# openmv-mp.net
KiCad netlist of a schematic drawn in EAGLE
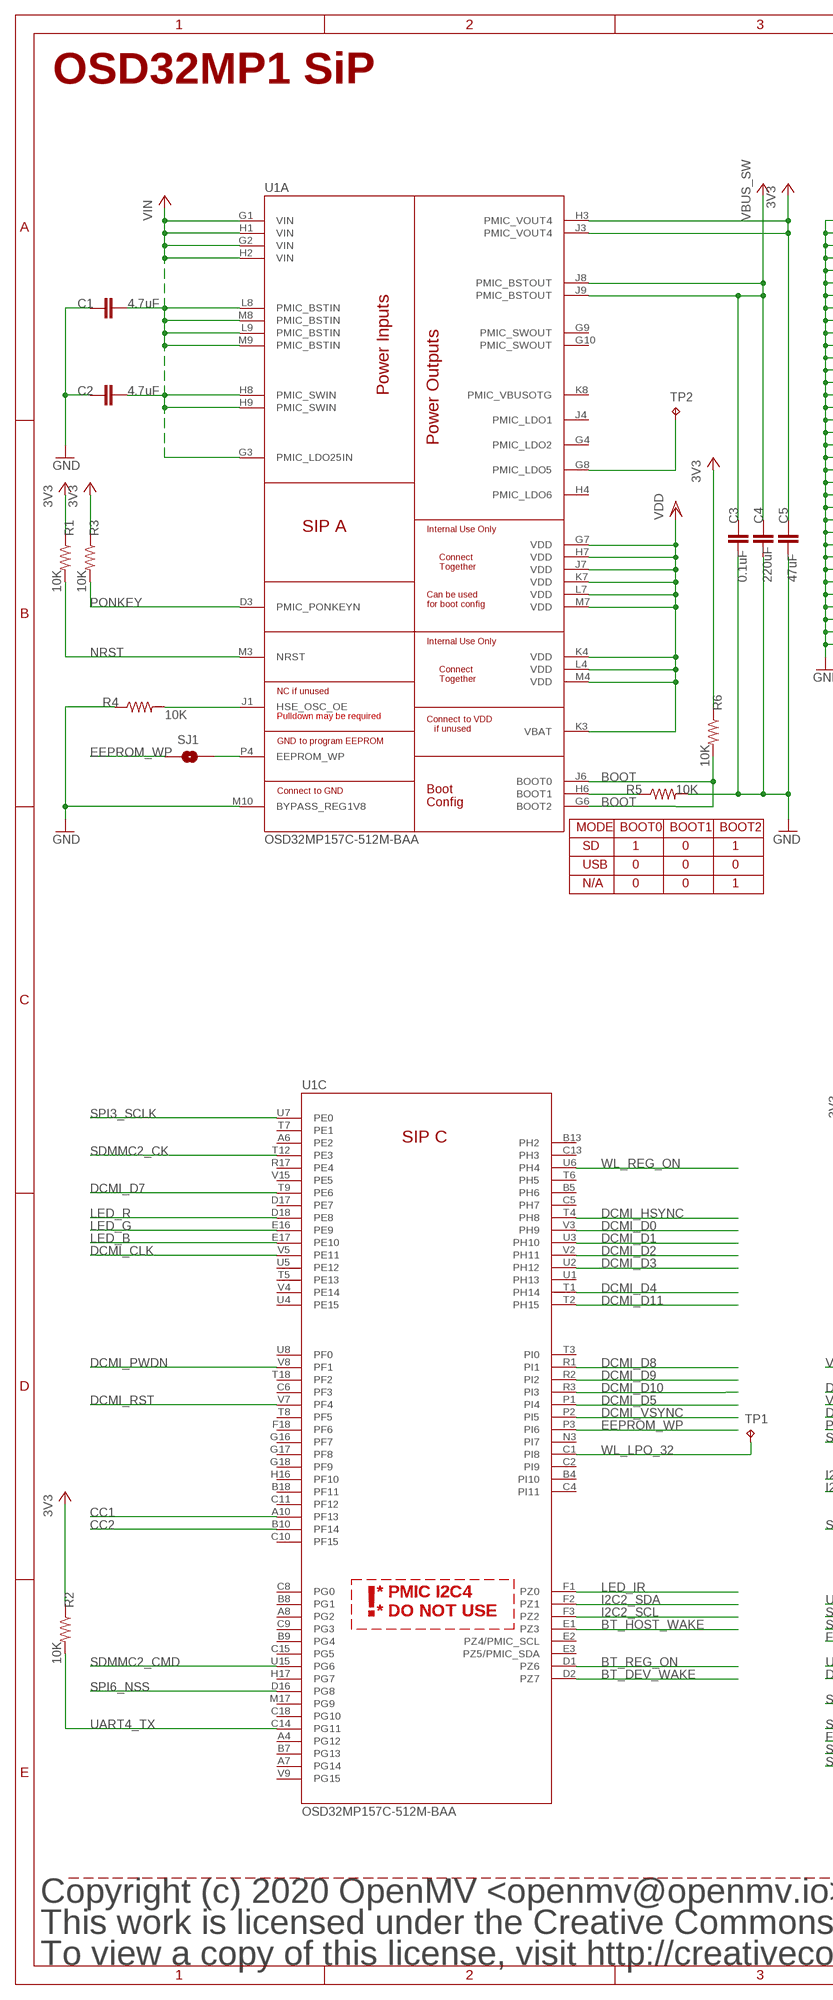
[diagram p0: schematic, sheet 1, part 1 of 2]
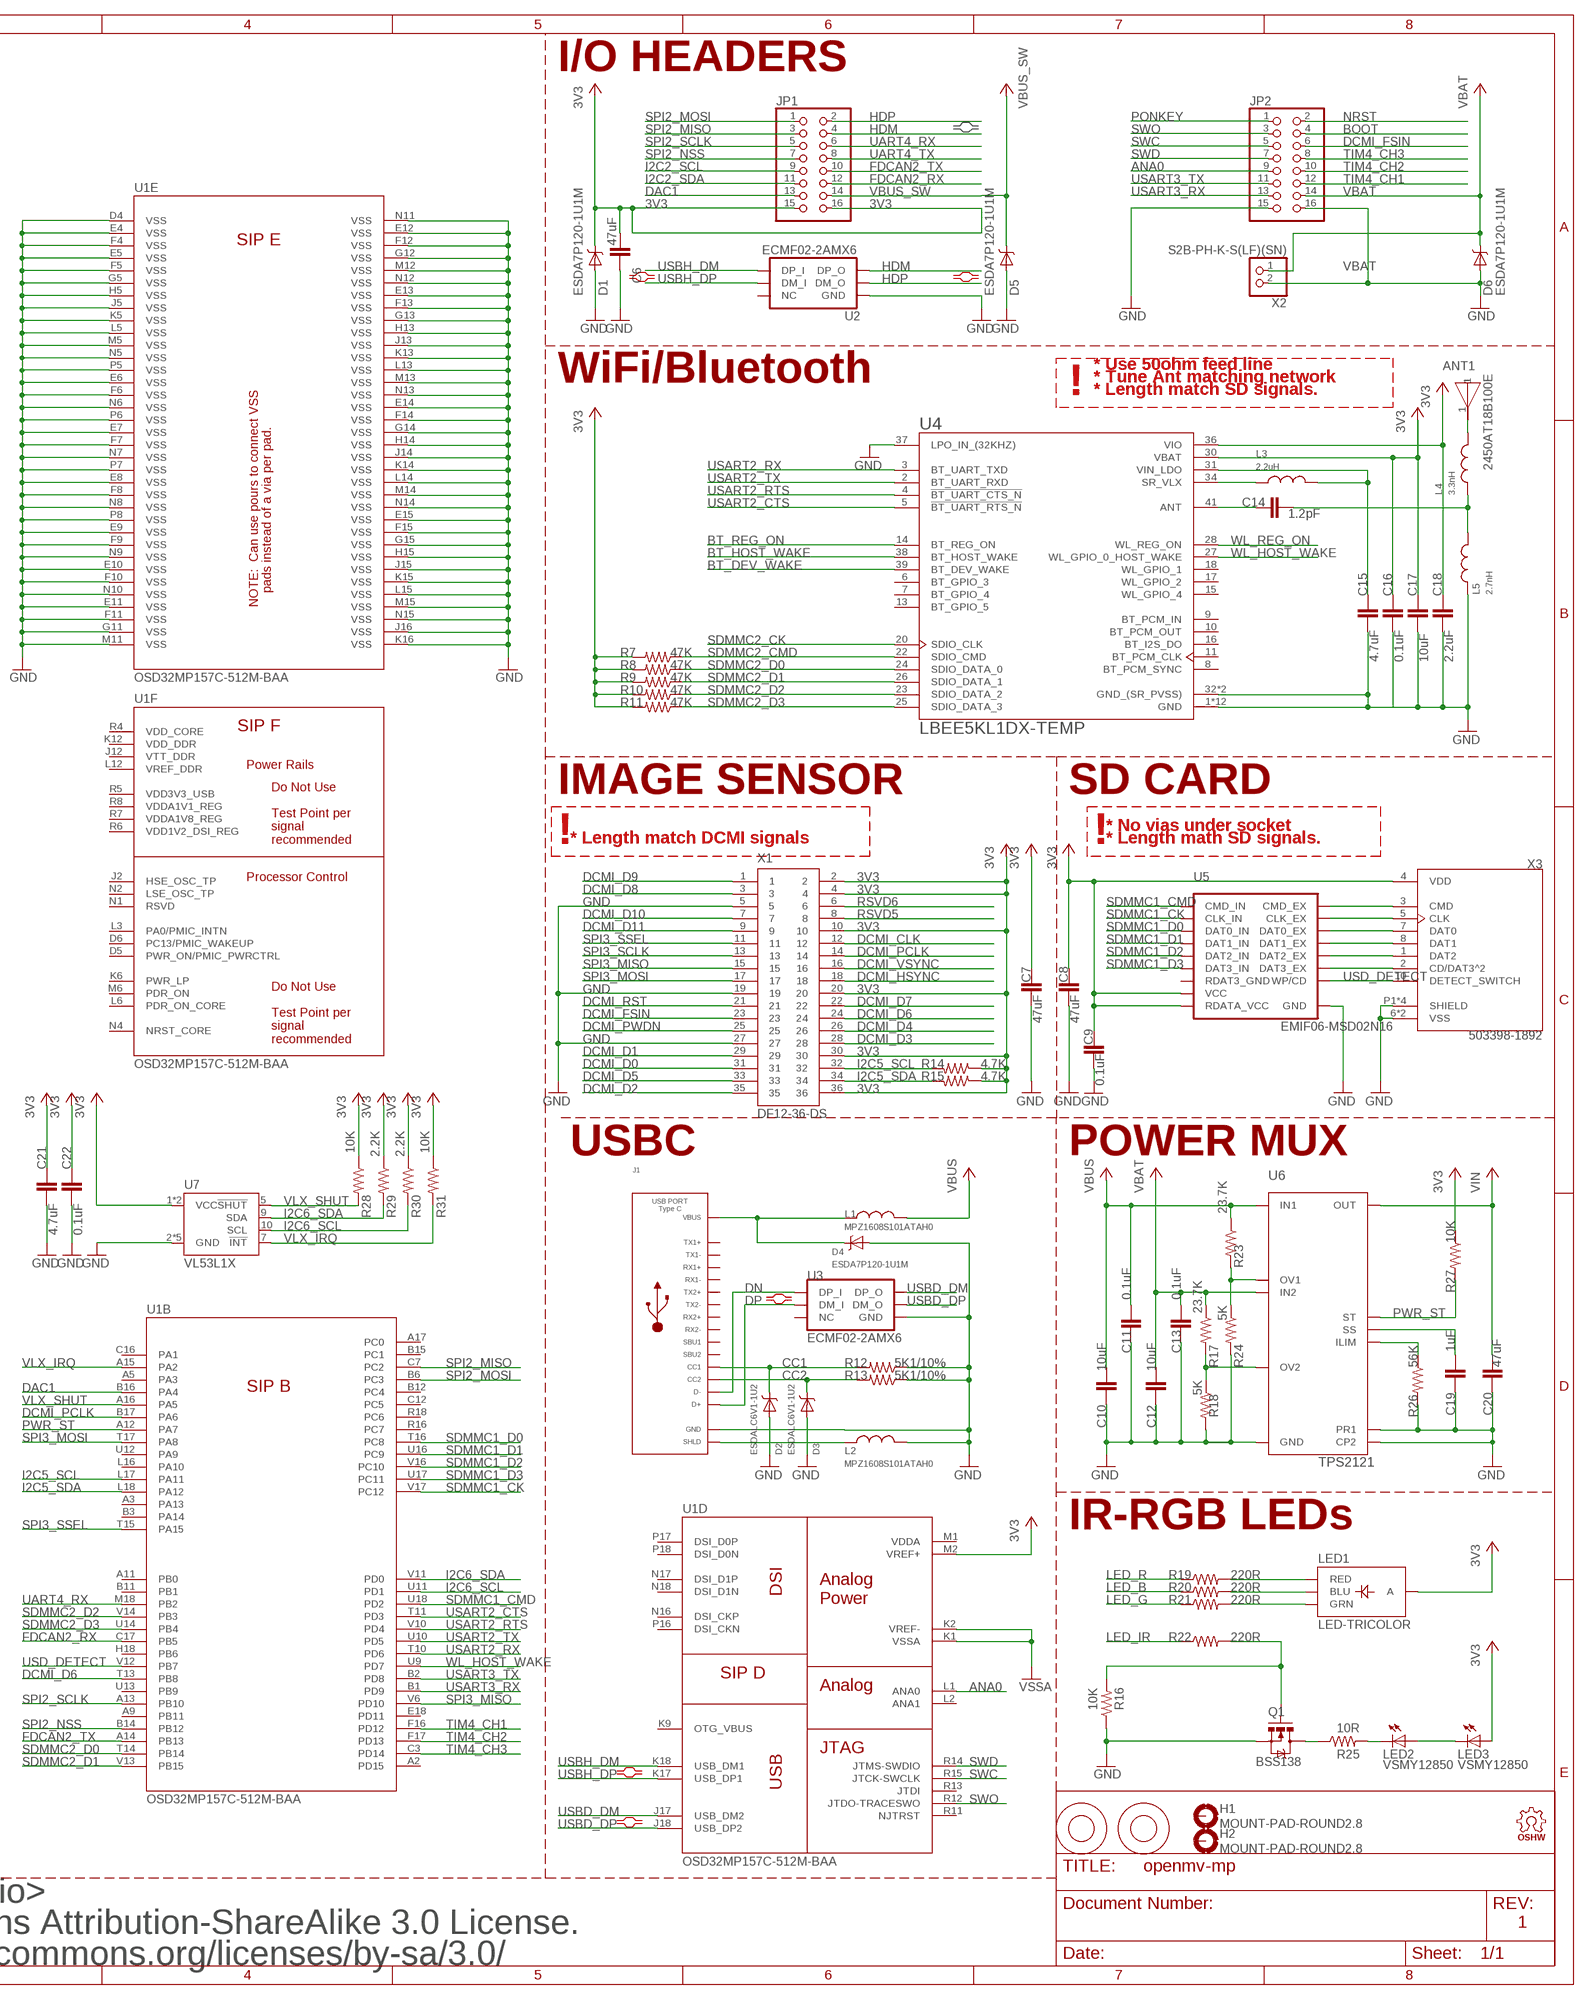
[diagram p1: schematic, sheet 1, part 2 of 2]

(export (version "E")
  (design (tool "Eeschema 10.0.6"))
  (components
    (comp (ref "ANT1")
      (value "2450AT18B100E")
      (footprint "eagle-import:ANT_2450AT18B100E")
      (fields (field (name "MF") "Johanson Technology"))
      (libsource (lib "eagle-import") (part "2450AT18B100E"))
    )
    (comp (ref "C1")
      (value "4.7uF")
      (footprint "eagle-import:0402-CAP")
      (libsource (lib "eagle-import") (part "CAP0402-CAP"))
    )
    (comp (ref "C2")
      (value "4.7uF")
      (footprint "eagle-import:0402-CAP")
      (libsource (lib "eagle-import") (part "CAP0402-CAP"))
    )
    (comp (ref "C3")
      (value "0.1uF")
      (footprint "eagle-import:0402-CAP")
      (libsource (lib "eagle-import") (part "CAP0402-CAP"))
    )
    (comp (ref "C4")
      (value "220uF")
      (footprint "eagle-import:1206")
      (libsource (lib "eagle-import") (part "CAP1206"))
    )
    (comp (ref "C5")
      (value "47uF")
      (footprint "eagle-import:0805")
      (libsource (lib "eagle-import") (part "CAP0805"))
    )
    (comp (ref "C6")
      (value "47uF")
      (footprint "eagle-import:0805")
      (libsource (lib "eagle-import") (part "CAP0805"))
    )
    (comp (ref "C7")
      (value "47uF")
      (footprint "eagle-import:0805")
      (libsource (lib "eagle-import") (part "CAP0805"))
    )
    (comp (ref "C8")
      (value "47uF")
      (footprint "eagle-import:0805")
      (libsource (lib "eagle-import") (part "CAP0805"))
    )
    (comp (ref "C9")
      (value "0.1uF")
      (footprint "eagle-import:0402-CAP")
      (libsource (lib "eagle-import") (part "CAP0402-CAP"))
    )
    (comp (ref "C10")
      (value "10uF")
      (footprint "eagle-import:0402-CAP")
      (libsource (lib "eagle-import") (part "CAP0402-CAP"))
    )
    (comp (ref "C11")
      (value "0.1uF")
      (footprint "eagle-import:0402-CAP")
      (libsource (lib "eagle-import") (part "CAP0402-CAP"))
    )
    (comp (ref "C12")
      (value "10uF")
      (footprint "eagle-import:0402-CAP")
      (libsource (lib "eagle-import") (part "CAP0402-CAP"))
    )
    (comp (ref "C13")
      (value "0.1uF")
      (footprint "eagle-import:0402-CAP")
      (libsource (lib "eagle-import") (part "CAP0402-CAP"))
    )
    (comp (ref "C14")
      (value "1.2pF")
      (footprint "eagle-import:0402-CAP")
      (libsource (lib "eagle-import") (part "CAP0402-CAP"))
    )
    (comp (ref "C15")
      (value "4.7uF")
      (footprint "eagle-import:0402-CAP")
      (libsource (lib "eagle-import") (part "CAP0402-CAP"))
    )
    (comp (ref "C16")
      (value "0.1uF")
      (footprint "eagle-import:0402-CAP")
      (libsource (lib "eagle-import") (part "CAP0402-CAP"))
    )
    (comp (ref "C17")
      (value "10uF")
      (footprint "eagle-import:0402-CAP")
      (libsource (lib "eagle-import") (part "CAP0402-CAP"))
    )
    (comp (ref "C18")
      (value "2.2uF")
      (footprint "eagle-import:0402-CAP")
      (libsource (lib "eagle-import") (part "CAP0402-CAP"))
    )
    (comp (ref "C19")
      (value "1uF")
      (footprint "eagle-import:0402-CAP")
      (libsource (lib "eagle-import") (part "CAP0402-CAP"))
    )
    (comp (ref "C20")
      (value "47uF")
      (footprint "eagle-import:0805")
      (libsource (lib "eagle-import") (part "CAP0805"))
    )
    (comp (ref "C21")
      (value "4.7uF")
      (footprint "eagle-import:0402-CAP")
      (libsource (lib "eagle-import") (part "CAP0402-CAP"))
    )
    (comp (ref "C22")
      (value "0.1uF")
      (footprint "eagle-import:0402-CAP")
      (libsource (lib "eagle-import") (part "CAP0402-CAP"))
    )
    (comp (ref "D1")
      (value "ESDA7P120-1U1M")
      (footprint "eagle-import:ST0603")
      (libsource (lib "eagle-import") (part "ESDA7P120-1U1M"))
    )
    (comp (ref "D2")
      (value "ESDALC6V1-1U2")
      (footprint "eagle-import:ST0201")
      (libsource (lib "eagle-import") (part "ESDALC6V1-1U2"))
    )
    (comp (ref "D3")
      (value "ESDALC6V1-1U2")
      (footprint "eagle-import:ST0201")
      (libsource (lib "eagle-import") (part "ESDALC6V1-1U2"))
    )
    (comp (ref "D4")
      (value "ESDA7P120-1U1M")
      (footprint "eagle-import:ST0603")
      (libsource (lib "eagle-import") (part "ESDA7P120-1U1M"))
    )
    (comp (ref "D5")
      (value "ESDA7P120-1U1M")
      (footprint "eagle-import:ST0603")
      (libsource (lib "eagle-import") (part "ESDA7P120-1U1M"))
    )
    (comp (ref "D6")
      (value "ESDA7P120-1U1M")
      (footprint "eagle-import:ST0603")
      (libsource (lib "eagle-import") (part "ESDA7P120-1U1M"))
    )
    (comp (ref "H1")
      (value "MOUNT-PAD-ROUND2.8")
      (footprint "eagle-import:2,8-PAD")
      (libsource (lib "eagle-import") (part "MOUNT-PAD-ROUND2.8"))
    )
    (comp (ref "H2")
      (value "MOUNT-PAD-ROUND2.8")
      (footprint "eagle-import:2,8-PAD")
      (libsource (lib "eagle-import") (part "MOUNT-PAD-ROUND2.8"))
    )
    (comp (ref "J1")
      (value "USB_TYPE-C_105450-0101")
      (footprint "eagle-import:105450-0101")
      (libsource (lib "eagle-import") (part "USB_TYPE-C_105450-0101"))
    )
    (comp (ref "JP1")
      (value "PINHD-2X8")
      (footprint "eagle-import:2X08")
      (libsource (lib "eagle-import") (part "PINHD-2X8"))
    )
    (comp (ref "JP2")
      (value "PINHD-2X8")
      (footprint "eagle-import:2X08")
      (libsource (lib "eagle-import") (part "PINHD-2X8"))
    )
    (comp (ref "L1")
      (value "MPZ1608S101ATAH0")
      (footprint "eagle-import:C0402")
      (libsource (lib "eagle-import") (part "INDUCTOR0402"))
    )
    (comp (ref "L2")
      (value "MPZ1608S101ATAH0")
      (footprint "eagle-import:C0402")
      (libsource (lib "eagle-import") (part "INDUCTOR0402"))
    )
    (comp (ref "L3")
      (value "2.2uH")
      (footprint "eagle-import:0603")
      (libsource (lib "eagle-import") (part "INDUCTOR0603"))
    )
    (comp (ref "L4")
      (value "3.3nH")
      (footprint "eagle-import:C0402")
      (libsource (lib "eagle-import") (part "INDUCTOR0402"))
    )
    (comp (ref "L5")
      (value "2.7nH")
      (footprint "eagle-import:C0402")
      (libsource (lib "eagle-import") (part "INDUCTOR0402"))
    )
    (comp (ref "LED1")
      (value "LED-TRICOLOR")
      (footprint "eagle-import:LED-TRICOLOR-SMD-MF")
      (libsource (lib "eagle-import") (part "LED-TRICOLOR"))
    )
    (comp (ref "LED2")
      (value "VSMY12850")
      (footprint "eagle-import:LED-1206")
      (libsource (lib "eagle-import") (part "LED1206"))
    )
    (comp (ref "LED3")
      (value "VSMY12850")
      (footprint "eagle-import:LED-1206")
      (libsource (lib "eagle-import") (part "LED1206"))
    )
    (comp (ref "LOGO1")
      (value "OSHW_LOGO_FILLX0100-NT")
      (footprint "eagle-import:OSHW_FILLX100_NOTEXT")
      (libsource (lib "eagle-import") (part "OSHW_LOGO_FILLX0100-NT"))
    )
    (comp (ref "M1")
      (value "9774030243R")
      (footprint "eagle-import:9774030151R")
      (libsource (lib "eagle-import") (part "9774030151R"))
    )
    (comp (ref "M2")
      (value "9774030243R")
      (footprint "eagle-import:9774030151R")
      (libsource (lib "eagle-import") (part "9774030151R"))
    )
    (comp (ref "Q1")
      (value "BSS138")
      (footprint "eagle-import:SOT23-3")
      (libsource (lib "eagle-import") (part "MOSFET-NCHANNELSMD"))
    )
    (comp (ref "R1")
      (value "10K")
      (footprint "eagle-import:0402-RES")
      (libsource (lib "eagle-import") (part "RESISTOR0402-RES"))
    )
    (comp (ref "R2")
      (value "10K")
      (footprint "eagle-import:0402-RES")
      (libsource (lib "eagle-import") (part "RESISTOR0402-RES"))
    )
    (comp (ref "R3")
      (value "10K")
      (footprint "eagle-import:0402-RES")
      (libsource (lib "eagle-import") (part "RESISTOR0402-RES"))
    )
    (comp (ref "R4")
      (value "10K")
      (footprint "eagle-import:0402-RES")
      (libsource (lib "eagle-import") (part "RESISTOR0402-RES"))
    )
    (comp (ref "R5")
      (value "10K")
      (footprint "eagle-import:0402-RES")
      (libsource (lib "eagle-import") (part "RESISTOR0402-RES"))
    )
    (comp (ref "R6")
      (value "10K")
      (footprint "eagle-import:0402-RES")
      (libsource (lib "eagle-import") (part "RESISTOR0402-RES"))
    )
    (comp (ref "R7")
      (value "47K")
      (footprint "eagle-import:0402-RES")
      (libsource (lib "eagle-import") (part "RESISTOR0402-RES"))
    )
    (comp (ref "R8")
      (value "47K")
      (footprint "eagle-import:0402-RES")
      (libsource (lib "eagle-import") (part "RESISTOR0402-RES"))
    )
    (comp (ref "R9")
      (value "47K")
      (footprint "eagle-import:0402-RES")
      (libsource (lib "eagle-import") (part "RESISTOR0402-RES"))
    )
    (comp (ref "R10")
      (value "47K")
      (footprint "eagle-import:0402-RES")
      (libsource (lib "eagle-import") (part "RESISTOR0402-RES"))
    )
    (comp (ref "R11")
      (value "47K")
      (footprint "eagle-import:0402-RES")
      (libsource (lib "eagle-import") (part "RESISTOR0402-RES"))
    )
    (comp (ref "R12")
      (value "5K1/10%")
      (footprint "eagle-import:0402-RES")
      (libsource (lib "eagle-import") (part "RESISTOR0402-RES"))
    )
    (comp (ref "R13")
      (value "5K1/10%")
      (footprint "eagle-import:0402-RES")
      (libsource (lib "eagle-import") (part "RESISTOR0402-RES"))
    )
    (comp (ref "R14")
      (value "4.7K")
      (footprint "eagle-import:0402-RES")
      (libsource (lib "eagle-import") (part "RESISTOR0402-RES"))
    )
    (comp (ref "R15")
      (value "4.7K")
      (footprint "eagle-import:0402-RES")
      (libsource (lib "eagle-import") (part "RESISTOR0402-RES"))
    )
    (comp (ref "R16")
      (value "10K")
      (footprint "eagle-import:0402-RES")
      (libsource (lib "eagle-import") (part "RESISTOR0402-RES"))
    )
    (comp (ref "R17")
      (value "23.7K")
      (footprint "eagle-import:0402-RES")
      (libsource (lib "eagle-import") (part "RESISTOR0402-RES"))
    )
    (comp (ref "R18")
      (value "5K")
      (footprint "eagle-import:0402-RES")
      (libsource (lib "eagle-import") (part "RESISTOR0402-RES"))
    )
    (comp (ref "R19")
      (value "220R")
      (footprint "eagle-import:0402-RES")
      (libsource (lib "eagle-import") (part "RESISTOR0402-RES"))
    )
    (comp (ref "R20")
      (value "220R")
      (footprint "eagle-import:0402-RES")
      (libsource (lib "eagle-import") (part "RESISTOR0402-RES"))
    )
    (comp (ref "R21")
      (value "220R")
      (footprint "eagle-import:0402-RES")
      (libsource (lib "eagle-import") (part "RESISTOR0402-RES"))
    )
    (comp (ref "R22")
      (value "220R")
      (footprint "eagle-import:0402-RES")
      (libsource (lib "eagle-import") (part "RESISTOR0402-RES"))
    )
    (comp (ref "R23")
      (value "23.7K")
      (footprint "eagle-import:0402-RES")
      (libsource (lib "eagle-import") (part "RESISTOR0402-RES"))
    )
    (comp (ref "R24")
      (value "5K")
      (footprint "eagle-import:0402-RES")
      (libsource (lib "eagle-import") (part "RESISTOR0402-RES"))
    )
    (comp (ref "R25")
      (value "10R")
      (footprint "eagle-import:0402-RES")
      (libsource (lib "eagle-import") (part "RESISTOR0402-RES"))
    )
    (comp (ref "R26")
      (value "56K")
      (footprint "eagle-import:0402-RES")
      (libsource (lib "eagle-import") (part "RESISTOR0402-RES"))
    )
    (comp (ref "R27")
      (value "10K")
      (footprint "eagle-import:0402-RES")
      (libsource (lib "eagle-import") (part "RESISTOR0402-RES"))
    )
    (comp (ref "R28")
      (value "10K")
      (footprint "eagle-import:0402-RES")
      (libsource (lib "eagle-import") (part "RESISTOR0402-RES"))
    )
    (comp (ref "R29")
      (value "2.2K")
      (footprint "eagle-import:0402-RES")
      (libsource (lib "eagle-import") (part "RESISTOR0402-RES"))
    )
    (comp (ref "R30")
      (value "2.2K")
      (footprint "eagle-import:0402-RES")
      (libsource (lib "eagle-import") (part "RESISTOR0402-RES"))
    )
    (comp (ref "R31")
      (value "10K")
      (footprint "eagle-import:0402-RES")
      (libsource (lib "eagle-import") (part "RESISTOR0402-RES"))
    )
    (comp (ref "SJ1")
      (value "SOLDERJUMPERNO")
      (footprint "eagle-import:SJ_2S-NO")
      (libsource (lib "eagle-import") (part "SOLDERJUMPERNO"))
    )
    (comp (ref "TP1")
      (value "TPTP10R")
      (footprint "eagle-import:TP10R")
      (libsource (lib "eagle-import") (part "TPTP10R"))
    )
    (comp (ref "TP2")
      (value "TPTP10R")
      (footprint "eagle-import:TP10R")
      (libsource (lib "eagle-import") (part "TPTP10R"))
    )
    (comp (ref "U1")
      (value "OSD32MP157C-512M-BAA")
      (footprint "eagle-import:OSD32MP15X-BGA-324")
      (libsource (lib "eagle-import") (part "OSD32MP157C-512M-BAA"))
    )
    (comp (ref "U2")
      (value "ECMF02-2AMX6")
      (footprint "eagle-import:QFN-6L")
      (libsource (lib "eagle-import") (part "ECMF02-2AMX6"))
    )
    (comp (ref "U3")
      (value "ECMF02-2AMX6")
      (footprint "eagle-import:QFN-6L")
      (libsource (lib "eagle-import") (part "ECMF02-2AMX6"))
    )
    (comp (ref "U4")
      (value "LBEE5KL1DX-TEMP")
      (footprint "eagle-import:XCVR_LBEE5KL1DX-TEMP")
      (fields (field (name "MF") "Murata Electronics"))
      (libsource (lib "eagle-import") (part "LBEE5KL1DX-TEMP"))
    )
    (comp (ref "U5")
      (value "EMIF06-MSD02N16")
      (footprint "eagle-import:QFN3.5")
      (libsource (lib "eagle-import") (part "EMIF06-MSD02N16"))
    )
    (comp (ref "U6")
      (value "TPS2121")
      (footprint "eagle-import:VQFN-HR")
      (libsource (lib "eagle-import") (part "TPS2121"))
    )
    (comp (ref "U7")
      (value "VL53L1X")
      (footprint "eagle-import:VL53L1X")
      (libsource (lib "eagle-import") (part "VL53L1XSMD"))
    )
    (comp (ref "X1")
      (value "DF12-36-DS")
      (footprint "eagle-import:DF12-36-DS")
      (libsource (lib "eagle-import") (part "DF12-36-DS"))
    )
    (comp (ref "X2")
      (value "S2B-PH-K-S(LF)(SN)")
      (footprint "eagle-import:JST-PH-2-THM-RA")
      (libsource (lib "eagle-import") (part "JST_2PIN-THM-RA"))
    )
    (comp (ref "X3")
      (value "503398-1892")
      (footprint "eagle-import:MOLEX_503398-1892")
      (fields (field (name "MF") "Molex") (field (name "MP") "5033981892"))
      (libsource (lib "eagle-import") (part "503398-1892"))
    )
  )
  (nets
    (net (code "1") (name "/ANA0") (class "Default")
      (node (ref "JP2") (pin "9") (pinfunction "9_9") (pintype "passive"))
      (node (ref "U1") (pin "L1") (pinfunction "ANA0_L1") (pintype "bidirectional"))
    )
    (net (code "2") (name "/BOOT") (class "Default")
      (node (ref "JP2") (pin "4") (pinfunction "4_4") (pintype "passive"))
      (node (ref "R6") (pin "2") (pinfunction "2_2") (pintype "passive"))
      (node (ref "U1") (pin "G6") (pinfunction "BOOT2_G6") (pintype "bidirectional"))
      (node (ref "U1") (pin "J6") (pinfunction "BOOT0_J6") (pintype "bidirectional"))
    )
    (net (code "3") (name "/BT_DEV_WAKE") (class "Default")
      (node (ref "U1") (pin "D2") (pinfunction "PZ7_D2") (pintype "bidirectional"))
      (node (ref "U4") (pin "39") (pinfunction "BT_DEV_WAKE_39") (pintype "bidirectional"))
    )
    (net (code "4") (name "/BT_HOST_WAKE") (class "Default")
      (node (ref "U1") (pin "E1") (pinfunction "PZ3_E1") (pintype "bidirectional"))
      (node (ref "U4") (pin "38") (pinfunction "BT_HOST_WAKE_38") (pintype "bidirectional"))
    )
    (net (code "5") (name "/BT_REG_ON") (class "Default")
      (node (ref "U1") (pin "D1") (pinfunction "PZ6_D1") (pintype "bidirectional"))
      (node (ref "U4") (pin "14") (pinfunction "BT_REG_ON_14") (pintype "input"))
    )
    (net (code "6") (name "/CC1") (class "Default")
      (node (ref "D2") (pin "1") (pinfunction "C_1") (pintype "passive"))
      (node (ref "J1") (pin "A5") (pinfunction "CC1_A5") (pintype "bidirectional"))
      (node (ref "R12") (pin "2") (pinfunction "2_2") (pintype "passive"))
      (node (ref "U1") (pin "A10") (pinfunction "PF13_A10") (pintype "bidirectional"))
    )
    (net (code "7") (name "/CC2") (class "Default")
      (node (ref "D3") (pin "1") (pinfunction "C_1") (pintype "passive"))
      (node (ref "J1") (pin "B5") (pinfunction "CC2_B5") (pintype "bidirectional"))
      (node (ref "R13") (pin "2") (pinfunction "2_2") (pintype "passive"))
      (node (ref "U1") (pin "B10") (pinfunction "PF14_B10") (pintype "bidirectional"))
    )
    (net (code "8") (name "/DAC1") (class "Default")
      (node (ref "JP1") (pin "13") (pinfunction "13_13") (pintype "passive"))
      (node (ref "U1") (pin "B16") (pinfunction "PA4_B16") (pintype "bidirectional"))
    )
    (net (code "9") (name "/DCMI_CLK") (class "Default")
      (node (ref "U1") (pin "V5") (pinfunction "PE11_V5") (pintype "bidirectional"))
      (node (ref "X1") (pin "12") (pinfunction "12_12") (pintype "bidirectional"))
    )
    (net (code "10") (name "/DCMI_D0") (class "Default")
      (node (ref "U1") (pin "V3") (pinfunction "PH9_V3") (pintype "bidirectional"))
      (node (ref "X1") (pin "31") (pinfunction "31_31") (pintype "bidirectional"))
    )
    (net (code "11") (name "/DCMI_D1") (class "Default")
      (node (ref "U1") (pin "U3") (pinfunction "PH10_U3") (pintype "bidirectional"))
      (node (ref "X1") (pin "29") (pinfunction "29_29") (pintype "bidirectional"))
    )
    (net (code "12") (name "/DCMI_D2") (class "Default")
      (node (ref "U1") (pin "V2") (pinfunction "PH11_V2") (pintype "bidirectional"))
      (node (ref "X1") (pin "35") (pinfunction "35_35") (pintype "bidirectional"))
    )
    (net (code "13") (name "/DCMI_D3") (class "Default")
      (node (ref "U1") (pin "U2") (pinfunction "PH12_U2") (pintype "bidirectional"))
      (node (ref "X1") (pin "28") (pinfunction "28_28") (pintype "bidirectional"))
    )
    (net (code "14") (name "/DCMI_D4") (class "Default")
      (node (ref "U1") (pin "T1") (pinfunction "PH14_T1") (pintype "bidirectional"))
      (node (ref "X1") (pin "26") (pinfunction "26_26") (pintype "bidirectional"))
    )
    (net (code "15") (name "/DCMI_D5") (class "Default")
      (node (ref "U1") (pin "P1") (pinfunction "PI4_P1") (pintype "bidirectional"))
      (node (ref "X1") (pin "33") (pinfunction "33_33") (pintype "bidirectional"))
    )
    (net (code "16") (name "/DCMI_D6") (class "Default")
      (node (ref "U1") (pin "T13") (pinfunction "PB8_T13") (pintype "bidirectional"))
      (node (ref "X1") (pin "24") (pinfunction "24_24") (pintype "bidirectional"))
    )
    (net (code "17") (name "/DCMI_D7") (class "Default")
      (node (ref "U1") (pin "T9") (pinfunction "PE6_T9") (pintype "bidirectional"))
      (node (ref "X1") (pin "22") (pinfunction "22_22") (pintype "bidirectional"))
    )
    (net (code "18") (name "/DCMI_D8") (class "Default")
      (node (ref "U1") (pin "R1") (pinfunction "PI1_R1") (pintype "bidirectional"))
      (node (ref "X1") (pin "3") (pinfunction "3_3") (pintype "bidirectional"))
    )
    (net (code "19") (name "/DCMI_D9") (class "Default")
      (node (ref "U1") (pin "R2") (pinfunction "PI2_R2") (pintype "bidirectional"))
      (node (ref "X1") (pin "1") (pinfunction "1_1") (pintype "bidirectional"))
    )
    (net (code "20") (name "/DCMI_D10") (class "Default")
      (node (ref "U1") (pin "R3") (pinfunction "PI3_R3") (pintype "bidirectional"))
      (node (ref "X1") (pin "7") (pinfunction "7_7") (pintype "bidirectional"))
    )
    (net (code "21") (name "/DCMI_D11") (class "Default")
      (node (ref "U1") (pin "T2") (pinfunction "PH15_T2") (pintype "bidirectional"))
      (node (ref "X1") (pin "9") (pinfunction "9_9") (pintype "bidirectional"))
    )
    (net (code "22") (name "/DCMI_FSIN") (class "Default")
      (node (ref "JP2") (pin "6") (pinfunction "6_6") (pintype "passive"))
      (node (ref "X1") (pin "23") (pinfunction "23_23") (pintype "bidirectional"))
    )
    (net (code "23") (name "/DCMI_HSYNC") (class "Default")
      (node (ref "U1") (pin "T4") (pinfunction "PH8_T4") (pintype "bidirectional"))
      (node (ref "X1") (pin "18") (pinfunction "18_18") (pintype "bidirectional"))
    )
    (net (code "24") (name "/DCMI_PCLK") (class "Default")
      (node (ref "U1") (pin "B17") (pinfunction "PA6_B17") (pintype "bidirectional"))
      (node (ref "X1") (pin "14") (pinfunction "14_14") (pintype "bidirectional"))
    )
    (net (code "25") (name "/DCMI_PWDN") (class "Default")
      (node (ref "U1") (pin "V8") (pinfunction "PF1_V8") (pintype "bidirectional"))
      (node (ref "X1") (pin "25") (pinfunction "25_25") (pintype "bidirectional"))
    )
    (net (code "26") (name "/DCMI_RST") (class "Default")
      (node (ref "U1") (pin "V7") (pinfunction "PF4_V7") (pintype "bidirectional"))
      (node (ref "X1") (pin "21") (pinfunction "21_21") (pintype "bidirectional"))
    )
    (net (code "27") (name "/DCMI_VSYNC") (class "Default")
      (node (ref "U1") (pin "P2") (pinfunction "PI5_P2") (pintype "bidirectional"))
      (node (ref "X1") (pin "16") (pinfunction "16_16") (pintype "bidirectional"))
    )
    (net (code "28") (name "/DN") (class "Default")
      (node (ref "J1") (pin "A7") (pinfunction "D-_A7") (pintype "bidirectional"))
      (node (ref "J1") (pin "B7") (pinfunction "D-_B7") (pintype "bidirectional"))
      (node (ref "U3") (pin "1") (pinfunction "DP_I_1") (pintype "input"))
    )
    (net (code "29") (name "/DP") (class "Default")
      (node (ref "J1") (pin "A6") (pinfunction "D+_A6") (pintype "bidirectional"))
      (node (ref "J1") (pin "B6") (pinfunction "D+_B6") (pintype "bidirectional"))
      (node (ref "U3") (pin "2") (pinfunction "DM_I_2") (pintype "input"))
    )
    (net (code "30") (name "/EEPROM_WP") (class "Default")
      (node (ref "SJ1") (pin "1") (pinfunction "1_1") (pintype "passive"))
      (node (ref "U1") (pin "P3") (pinfunction "PI6_P3") (pintype "bidirectional"))
    )
    (net (code "31") (name "/FDCAN2_RX") (class "Default")
      (node (ref "JP1") (pin "12") (pinfunction "12_12") (pintype "passive"))
      (node (ref "U1") (pin "C17") (pinfunction "PB5_C17") (pintype "bidirectional"))
    )
    (net (code "32") (name "/FDCAN2_TX") (class "Default")
      (node (ref "JP1") (pin "10") (pinfunction "10_10") (pintype "passive"))
      (node (ref "U1") (pin "A14") (pinfunction "PB13_A14") (pintype "bidirectional"))
    )
    (net (code "33") (name "/HDM") (class "Default")
      (node (ref "JP1") (pin "4") (pinfunction "4_4") (pintype "passive"))
      (node (ref "U2") (pin "6") (pinfunction "DP_O_6") (pintype "output"))
    )
    (net (code "34") (name "/HDP") (class "Default")
      (node (ref "JP1") (pin "2") (pinfunction "2_2") (pintype "passive"))
      (node (ref "U2") (pin "5") (pinfunction "DM_O_5") (pintype "output"))
    )
    (net (code "35") (name "/I2C2_SCL") (class "Default")
      (node (ref "JP1") (pin "9") (pinfunction "9_9") (pintype "passive"))
      (node (ref "U1") (pin "F3") (pinfunction "PZ2_F3") (pintype "bidirectional"))
    )
    (net (code "36") (name "/I2C2_SDA") (class "Default")
      (node (ref "JP1") (pin "11") (pinfunction "11_11") (pintype "passive"))
      (node (ref "U1") (pin "F2") (pinfunction "PZ1_F2") (pintype "bidirectional"))
    )
    (net (code "37") (name "/I2C5_SCL") (class "Default")
      (node (ref "R14") (pin "2") (pinfunction "2_2") (pintype "passive"))
      (node (ref "U1") (pin "L17") (pinfunction "PA11_L17") (pintype "bidirectional"))
      (node (ref "X1") (pin "32") (pinfunction "32_32") (pintype "bidirectional"))
    )
    (net (code "38") (name "/I2C5_SDA") (class "Default")
      (node (ref "R15") (pin "2") (pinfunction "2_2") (pintype "passive"))
      (node (ref "U1") (pin "L18") (pinfunction "PA12_L18") (pintype "bidirectional"))
      (node (ref "X1") (pin "34") (pinfunction "34_34") (pintype "bidirectional"))
    )
    (net (code "39") (name "/I2C6_SCL") (class "Default")
      (node (ref "R30") (pin "2") (pinfunction "2_2") (pintype "passive"))
      (node (ref "U1") (pin "U11") (pinfunction "PD1_U11") (pintype "bidirectional"))
      (node (ref "U7") (pin "10") (pinfunction "SCL_10") (pintype "bidirectional"))
    )
    (net (code "40") (name "/I2C6_SDA") (class "Default")
      (node (ref "R29") (pin "2") (pinfunction "2_2") (pintype "passive"))
      (node (ref "U1") (pin "V11") (pinfunction "PD0_V11") (pintype "bidirectional"))
      (node (ref "U7") (pin "9") (pinfunction "SDA_9") (pintype "bidirectional"))
    )
    (net (code "41") (name "/LED_B") (class "Default")
      (node (ref "R20") (pin "1") (pinfunction "1_1") (pintype "passive"))
      (node (ref "U1") (pin "E17") (pinfunction "PE10_E17") (pintype "bidirectional"))
    )
    (net (code "42") (name "/LED_G") (class "Default")
      (node (ref "R21") (pin "1") (pinfunction "1_1") (pintype "passive"))
      (node (ref "U1") (pin "E16") (pinfunction "PE9_E16") (pintype "bidirectional"))
    )
    (net (code "43") (name "/LED_IR") (class "Default")
      (node (ref "R22") (pin "1") (pinfunction "1_1") (pintype "passive"))
      (node (ref "U1") (pin "F1") (pinfunction "PZ0_F1") (pintype "bidirectional"))
    )
    (net (code "44") (name "/LED_R") (class "Default")
      (node (ref "R19") (pin "1") (pinfunction "1_1") (pintype "passive"))
      (node (ref "U1") (pin "D18") (pinfunction "PE8_D18") (pintype "bidirectional"))
    )
    (net (code "45") (name "/NRST") (class "Default")
      (node (ref "JP2") (pin "2") (pinfunction "2_2") (pintype "passive"))
      (node (ref "R1") (pin "2") (pinfunction "2_2") (pintype "passive"))
      (node (ref "U1") (pin "M3") (pinfunction "NRST_M3") (pintype "bidirectional"))
    )
    (net (code "46") (name "/PONKEY") (class "Default")
      (node (ref "JP2") (pin "1") (pinfunction "1_1") (pintype "passive"))
      (node (ref "R3") (pin "2") (pinfunction "2_2") (pintype "passive"))
      (node (ref "U1") (pin "D3") (pinfunction "PMIC_PONKEYN_D3") (pintype "bidirectional"))
    )
    (net (code "47") (name "/PWR_ST") (class "Default")
      (node (ref "R27") (pin "2") (pinfunction "2_2") (pintype "passive"))
      (node (ref "U1") (pin "A12") (pinfunction "PA7_A12") (pintype "bidirectional"))
      (node (ref "U6") (pin "P$9") (pinfunction "ST_P$9") (pintype "output"))
    )
    (net (code "48") (name "/RSVD5") (class "Default")
      (node (ref "X1") (pin "8") (pinfunction "8_8") (pintype "bidirectional"))
    )
    (net (code "49") (name "/RSVD6") (class "Default")
      (node (ref "X1") (pin "6") (pinfunction "6_6") (pintype "bidirectional"))
    )
    (net (code "50") (name "/SDMMC1_CK") (class "Default")
      (node (ref "U1") (pin "V17") (pinfunction "PC12_V17") (pintype "bidirectional"))
      (node (ref "U5") (pin "P$6") (pinfunction "CLK_IN_P$6") (pintype "input"))
    )
    (net (code "51") (name "/SDMMC1_CMD") (class "Default")
      (node (ref "U1") (pin "U18") (pinfunction "PD2_U18") (pintype "bidirectional"))
      (node (ref "U5") (pin "P$5") (pinfunction "CMD_IN_P$5") (pintype "input"))
    )
    (net (code "52") (name "/SDMMC1_D0") (class "Default")
      (node (ref "U1") (pin "T16") (pinfunction "PC8_T16") (pintype "bidirectional"))
      (node (ref "U5") (pin "P$7") (pinfunction "DAT0_IN_P$7") (pintype "input"))
    )
    (net (code "53") (name "/SDMMC1_D1") (class "Default")
      (node (ref "U1") (pin "U16") (pinfunction "PC9_U16") (pintype "bidirectional"))
      (node (ref "U5") (pin "P$8") (pinfunction "DAT1_IN_P$8") (pintype "input"))
    )
    (net (code "54") (name "/SDMMC1_D2") (class "Default")
      (node (ref "U1") (pin "V16") (pinfunction "PC10_V16") (pintype "bidirectional"))
      (node (ref "U5") (pin "P$3") (pinfunction "DAT2_IN_P$3") (pintype "input"))
    )
    (net (code "55") (name "/SDMMC1_D3") (class "Default")
      (node (ref "U1") (pin "U17") (pinfunction "PC11_U17") (pintype "bidirectional"))
      (node (ref "U5") (pin "P$4") (pinfunction "DAT3_IN_P$4") (pintype "input"))
    )
    (net (code "56") (name "/SDMMC2_CK") (class "Default")
      (node (ref "U1") (pin "T12") (pinfunction "PE3_T12") (pintype "bidirectional"))
      (node (ref "U4") (pin "20") (pinfunction "SDIO_CLK_20") (pintype "input"))
    )
    (net (code "57") (name "/SDMMC2_CMD") (class "Default")
      (node (ref "R7") (pin "1") (pinfunction "1_1") (pintype "passive"))
      (node (ref "U1") (pin "U15") (pinfunction "PG6_U15") (pintype "bidirectional"))
      (node (ref "U4") (pin "22") (pinfunction "SDIO_CMD_22") (pintype "bidirectional"))
    )
    (net (code "58") (name "/SDMMC2_D0") (class "Default")
      (node (ref "R8") (pin "1") (pinfunction "1_1") (pintype "passive"))
      (node (ref "U1") (pin "T14") (pinfunction "PB14_T14") (pintype "bidirectional"))
      (node (ref "U4") (pin "24") (pinfunction "SDIO_DATA_0_24") (pintype "bidirectional"))
    )
    (net (code "59") (name "/SDMMC2_D1") (class "Default")
      (node (ref "R9") (pin "1") (pinfunction "1_1") (pintype "passive"))
      (node (ref "U1") (pin "V13") (pinfunction "PB15_V13") (pintype "bidirectional"))
      (node (ref "U4") (pin "26") (pinfunction "SDIO_DATA_1_26") (pintype "bidirectional"))
    )
    (net (code "60") (name "/SDMMC2_D2") (class "Default")
      (node (ref "R10") (pin "1") (pinfunction "1_1") (pintype "passive"))
      (node (ref "U1") (pin "V14") (pinfunction "PB3_V14") (pintype "bidirectional"))
      (node (ref "U4") (pin "23") (pinfunction "SDIO_DATA_2_23") (pintype "bidirectional"))
    )
    (net (code "61") (name "/SDMMC2_D3") (class "Default")
      (node (ref "R11") (pin "1") (pinfunction "1_1") (pintype "passive"))
      (node (ref "U1") (pin "U14") (pinfunction "PB4_U14") (pintype "bidirectional"))
      (node (ref "U4") (pin "25") (pinfunction "SDIO_DATA_3_25") (pintype "bidirectional"))
    )
    (net (code "62") (name "/SPI2_MISO") (class "Default")
      (node (ref "JP1") (pin "3") (pinfunction "3_3") (pintype "passive"))
      (node (ref "U1") (pin "C7") (pinfunction "PC2_C7") (pintype "bidirectional"))
    )
    (net (code "63") (name "/SPI2_MOSI") (class "Default")
      (node (ref "JP1") (pin "1") (pinfunction "1_1") (pintype "passive"))
      (node (ref "U1") (pin "B6") (pinfunction "PC3_B6") (pintype "bidirectional"))
    )
    (net (code "64") (name "/SPI2_NSS") (class "Default")
      (node (ref "JP1") (pin "7") (pinfunction "7_7") (pintype "passive"))
      (node (ref "U1") (pin "B14") (pinfunction "PB12_B14") (pintype "bidirectional"))
    )
    (net (code "65") (name "/SPI2_SCLK") (class "Default")
      (node (ref "JP1") (pin "5") (pinfunction "5_5") (pintype "passive"))
      (node (ref "U1") (pin "A13") (pinfunction "PB10_A13") (pintype "bidirectional"))
    )
    (net (code "66") (name "/SPI3_MISO") (class "Default")
      (node (ref "U1") (pin "V6") (pinfunction "PD10_V6") (pintype "bidirectional"))
      (node (ref "X1") (pin "15") (pinfunction "15_15") (pintype "bidirectional"))
    )
    (net (code "67") (name "/SPI3_MOSI") (class "Default")
      (node (ref "U1") (pin "T17") (pinfunction "PA8_T17") (pintype "bidirectional"))
      (node (ref "X1") (pin "17") (pinfunction "17_17") (pintype "bidirectional"))
    )
    (net (code "68") (name "/SPI3_SCLK") (class "Default")
      (node (ref "U1") (pin "U7") (pinfunction "PE0_U7") (pintype "bidirectional"))
      (node (ref "X1") (pin "13") (pinfunction "13_13") (pintype "bidirectional"))
    )
    (net (code "69") (name "/SPI3_SSEL") (class "Default")
      (node (ref "U1") (pin "T15") (pinfunction "PA15_T15") (pintype "bidirectional"))
      (node (ref "X1") (pin "11") (pinfunction "11_11") (pintype "bidirectional"))
    )
    (net (code "70") (name "/SPI6_NSS") (class "Default")
      (node (ref "U1") (pin "D16") (pinfunction "PG8_D16") (pintype "bidirectional"))
    )
    (net (code "71") (name "/SWC") (class "Default")
      (node (ref "JP2") (pin "5") (pinfunction "5_5") (pintype "passive"))
      (node (ref "U1") (pin "R15") (pinfunction "JTCK-SWCLK_R15") (pintype "bidirectional"))
    )
    (net (code "72") (name "/SWD") (class "Default")
      (node (ref "JP2") (pin "7") (pinfunction "7_7") (pintype "passive"))
      (node (ref "U1") (pin "R14") (pinfunction "JTMS-SWDIO_R14") (pintype "bidirectional"))
    )
    (net (code "73") (name "/SWO") (class "Default")
      (node (ref "JP2") (pin "3") (pinfunction "3_3") (pintype "passive"))
      (node (ref "U1") (pin "R12") (pinfunction "JTDO-TRACESWO_R12") (pintype "bidirectional"))
    )
    (net (code "74") (name "/TIM4_CH1") (class "Default")
      (node (ref "JP2") (pin "12") (pinfunction "12_12") (pintype "passive"))
      (node (ref "U1") (pin "F16") (pinfunction "PD12_F16") (pintype "bidirectional"))
    )
    (net (code "75") (name "/TIM4_CH2") (class "Default")
      (node (ref "JP2") (pin "10") (pinfunction "10_10") (pintype "passive"))
      (node (ref "U1") (pin "F17") (pinfunction "PD13_F17") (pintype "bidirectional"))
    )
    (net (code "76") (name "/TIM4_CH3") (class "Default")
      (node (ref "JP2") (pin "8") (pinfunction "8_8") (pintype "passive"))
      (node (ref "U1") (pin "C3") (pinfunction "PD14_C3") (pintype "bidirectional"))
    )
    (net (code "77") (name "/UART4_RX") (class "Default")
      (node (ref "JP1") (pin "6") (pinfunction "6_6") (pintype "passive"))
      (node (ref "U1") (pin "M18") (pinfunction "PB2_M18") (pintype "bidirectional"))
    )
    (net (code "78") (name "/UART4_TX") (class "Default")
      (node (ref "JP1") (pin "8") (pinfunction "8_8") (pintype "passive"))
      (node (ref "R2") (pin "2") (pinfunction "2_2") (pintype "passive"))
      (node (ref "U1") (pin "C14") (pinfunction "PG11_C14") (pintype "bidirectional"))
    )
    (net (code "79") (name "/USART2_CTS") (class "Default")
      (node (ref "U1") (pin "T11") (pinfunction "PD3_T11") (pintype "bidirectional"))
      (node (ref "U4") (pin "5") (pinfunction "~{BT_UART_RTS_N}_5") (pintype "output"))
    )
    (net (code "80") (name "/USART2_RTS") (class "Default")
      (node (ref "U1") (pin "V10") (pinfunction "PD4_V10") (pintype "bidirectional"))
      (node (ref "U4") (pin "4") (pinfunction "~{BT_UART_CTS_N}_4") (pintype "input"))
    )
    (net (code "81") (name "/USART2_RX") (class "Default")
      (node (ref "U1") (pin "T10") (pinfunction "PD6_T10") (pintype "bidirectional"))
      (node (ref "U4") (pin "3") (pinfunction "BT_UART_TXD_3") (pintype "output"))
    )
    (net (code "82") (name "/USART2_TX") (class "Default")
      (node (ref "U1") (pin "U10") (pinfunction "PD5_U10") (pintype "bidirectional"))
      (node (ref "U4") (pin "2") (pinfunction "BT_UART_RXD_2") (pintype "input"))
    )
    (net (code "83") (name "/USART3_RX") (class "Default")
      (node (ref "JP2") (pin "13") (pinfunction "13_13") (pintype "passive"))
      (node (ref "U1") (pin "B1") (pinfunction "PD9_B1") (pintype "bidirectional"))
    )
    (net (code "84") (name "/USART3_TX") (class "Default")
      (node (ref "JP2") (pin "11") (pinfunction "11_11") (pintype "passive"))
      (node (ref "U1") (pin "B2") (pinfunction "PD8_B2") (pintype "bidirectional"))
    )
    (net (code "85") (name "/USBD_DM") (class "Default")
      (node (ref "U1") (pin "J17") (pinfunction "USB_DM2_J17") (pintype "bidirectional"))
      (node (ref "U3") (pin "6") (pinfunction "DP_O_6") (pintype "output"))
    )
    (net (code "86") (name "/USBD_DP") (class "Default")
      (node (ref "U1") (pin "J18") (pinfunction "USB_DP2_J18") (pintype "bidirectional"))
      (node (ref "U3") (pin "5") (pinfunction "DM_O_5") (pintype "output"))
    )
    (net (code "87") (name "/USBH_DM") (class "Default")
      (node (ref "U1") (pin "K18") (pinfunction "USB_DM1_K18") (pintype "bidirectional"))
      (node (ref "U2") (pin "1") (pinfunction "DP_I_1") (pintype "input"))
    )
    (net (code "88") (name "/USBH_DP") (class "Default")
      (node (ref "U1") (pin "K17") (pinfunction "USB_DP1_K17") (pintype "bidirectional"))
      (node (ref "U2") (pin "2") (pinfunction "DM_I_2") (pintype "input"))
    )
    (net (code "89") (name "/USD_DETECT") (class "Default")
      (node (ref "U1") (pin "V12") (pinfunction "PB7_V12") (pintype "bidirectional"))
      (node (ref "U5") (pin "P$1") (pinfunction "WP/CD_P$1") (pintype "input"))
      (node (ref "X3") (pin "10") (pinfunction "DETECT_SWITCH_10") (pintype "passive"))
    )
    (net (code "90") (name "/VLX_IRQ") (class "Default")
      (node (ref "R31") (pin "2") (pinfunction "2_2") (pintype "passive"))
      (node (ref "U1") (pin "A15") (pinfunction "PA2_A15") (pintype "bidirectional"))
      (node (ref "U7") (pin "7") (pinfunction "~{INT}_7") (pintype "bidirectional"))
    )
    (net (code "91") (name "/VLX_SHUT") (class "Default")
      (node (ref "R28") (pin "2") (pinfunction "2_2") (pintype "passive"))
      (node (ref "U1") (pin "A16") (pinfunction "PA5_A16") (pintype "bidirectional"))
      (node (ref "U7") (pin "5") (pinfunction "~{SHUT}_5") (pintype "bidirectional"))
    )
    (net (code "92") (name "/WL_HOST_WAKE") (class "Default")
      (node (ref "U1") (pin "U9") (pinfunction "PD7_U9") (pintype "bidirectional"))
      (node (ref "U4") (pin "27") (pinfunction "WL_GPIO_0_HOST_WAKE_27") (pintype "bidirectional"))
    )
    (net (code "93") (name "/WL_LPO_32") (class "Default")
      (node (ref "TP1") (pin "TP") (pinfunction "TP_TP") (pintype "input"))
      (node (ref "U1") (pin "C1") (pinfunction "PI8_C1") (pintype "bidirectional"))
    )
    (net (code "94") (name "/WL_REG_ON") (class "Default")
      (node (ref "U1") (pin "U6") (pinfunction "PH4_U6") (pintype "bidirectional"))
      (node (ref "U4") (pin "28") (pinfunction "WL_REG_ON_28") (pintype "input"))
    )
    (net (code "95") (name "3V3") (class "Default")
      (node (ref "C16") (pin "1") (pinfunction "1_1") (pintype "passive"))
      (node (ref "C17") (pin "1") (pinfunction "1_1") (pintype "passive"))
      (node (ref "C18") (pin "1") (pinfunction "1_1") (pintype "passive"))
      (node (ref "C21") (pin "1") (pinfunction "1_1") (pintype "passive"))
      (node (ref "C22") (pin "1") (pinfunction "1_1") (pintype "passive"))
      (node (ref "C5") (pin "1") (pinfunction "1_1") (pintype "passive"))
      (node (ref "C6") (pin "1") (pinfunction "1_1") (pintype "passive"))
      (node (ref "C7") (pin "1") (pinfunction "1_1") (pintype "passive"))
      (node (ref "C8") (pin "1") (pinfunction "1_1") (pintype "passive"))
      (node (ref "C9") (pin "1") (pinfunction "1_1") (pintype "passive"))
      (node (ref "D1") (pin "1") (pinfunction "C_1") (pintype "passive"))
      (node (ref "JP1") (pin "15") (pinfunction "15_15") (pintype "passive"))
      (node (ref "JP1") (pin "16") (pinfunction "16_16") (pintype "passive"))
      (node (ref "LED1") (pin "A") (pinfunction "A_A") (pintype "bidirectional"))
      (node (ref "LED3") (pin "A") (pinfunction "A_A") (pintype "passive"))
      (node (ref "R1") (pin "1") (pinfunction "1_1") (pintype "passive"))
      (node (ref "R10") (pin "2") (pinfunction "2_2") (pintype "passive"))
      (node (ref "R11") (pin "2") (pinfunction "2_2") (pintype "passive"))
      (node (ref "R14") (pin "1") (pinfunction "1_1") (pintype "passive"))
      (node (ref "R15") (pin "1") (pinfunction "1_1") (pintype "passive"))
      (node (ref "R2") (pin "1") (pinfunction "1_1") (pintype "passive"))
      (node (ref "R27") (pin "1") (pinfunction "1_1") (pintype "passive"))
      (node (ref "R28") (pin "1") (pinfunction "1_1") (pintype "passive"))
      (node (ref "R29") (pin "1") (pinfunction "1_1") (pintype "passive"))
      (node (ref "R3") (pin "1") (pinfunction "1_1") (pintype "passive"))
      (node (ref "R30") (pin "1") (pinfunction "1_1") (pintype "passive"))
      (node (ref "R31") (pin "1") (pinfunction "1_1") (pintype "passive"))
      (node (ref "R6") (pin "1") (pinfunction "1_1") (pintype "passive"))
      (node (ref "R7") (pin "2") (pinfunction "2_2") (pintype "passive"))
      (node (ref "R8") (pin "2") (pinfunction "2_2") (pintype "passive"))
      (node (ref "R9") (pin "2") (pinfunction "2_2") (pintype "passive"))
      (node (ref "U1") (pin "H3") (pinfunction "PMIC_VOUT4_H3") (pintype "bidirectional"))
      (node (ref "U1") (pin "J3") (pinfunction "PMIC_VOUT4_J3") (pintype "bidirectional"))
      (node (ref "U1") (pin "M2") (pinfunction "VREF+_M2") (pintype "bidirectional"))
      (node (ref "U4") (pin "30") (pinfunction "VBAT_30") (pintype "power_in"))
      (node (ref "U4") (pin "36") (pinfunction "VIO_36") (pintype "power_in"))
      (node (ref "U5") (pin "P$15") (pinfunction "VCC_P$15") (pintype "power_in"))
      (node (ref "U5") (pin "P$16") (pinfunction "RDATA_VCC_P$16") (pintype "passive"))
      (node (ref "U7") (pin "1") (pinfunction "VCC_1") (pintype "bidirectional"))
      (node (ref "U7") (pin "11") (pinfunction "VCC_11") (pintype "bidirectional"))
      (node (ref "X1") (pin "10") (pinfunction "10_10") (pintype "bidirectional"))
      (node (ref "X1") (pin "2") (pinfunction "2_2") (pintype "bidirectional"))
      (node (ref "X1") (pin "20") (pinfunction "20_20") (pintype "bidirectional"))
      (node (ref "X1") (pin "30") (pinfunction "30_30") (pintype "bidirectional"))
      (node (ref "X1") (pin "36") (pinfunction "36_36") (pintype "bidirectional"))
      (node (ref "X1") (pin "4") (pinfunction "4_4") (pintype "bidirectional"))
      (node (ref "X3") (pin "4") (pinfunction "VDD_4") (pintype "power_in"))
    )
    (net (code "96") (name "GND") (class "Default")
      (node (ref "C1") (pin "1") (pinfunction "1_1") (pintype "passive"))
      (node (ref "C10") (pin "2") (pinfunction "2_2") (pintype "passive"))
      (node (ref "C11") (pin "2") (pinfunction "2_2") (pintype "passive"))
      (node (ref "C12") (pin "2") (pinfunction "2_2") (pintype "passive"))
      (node (ref "C13") (pin "2") (pinfunction "2_2") (pintype "passive"))
      (node (ref "C15") (pin "2") (pinfunction "2_2") (pintype "passive"))
      (node (ref "C16") (pin "2") (pinfunction "2_2") (pintype "passive"))
      (node (ref "C17") (pin "2") (pinfunction "2_2") (pintype "passive"))
      (node (ref "C18") (pin "2") (pinfunction "2_2") (pintype "passive"))
      (node (ref "C19") (pin "2") (pinfunction "2_2") (pintype "passive"))
      (node (ref "C2") (pin "1") (pinfunction "1_1") (pintype "passive"))
      (node (ref "C20") (pin "2") (pinfunction "2_2") (pintype "passive"))
      (node (ref "C21") (pin "2") (pinfunction "2_2") (pintype "passive"))
      (node (ref "C22") (pin "2") (pinfunction "2_2") (pintype "passive"))
      (node (ref "C3") (pin "2") (pinfunction "2_2") (pintype "passive"))
      (node (ref "C4") (pin "2") (pinfunction "2_2") (pintype "passive"))
      (node (ref "C5") (pin "2") (pinfunction "2_2") (pintype "passive"))
      (node (ref "C6") (pin "2") (pinfunction "2_2") (pintype "passive"))
      (node (ref "C7") (pin "2") (pinfunction "2_2") (pintype "passive"))
      (node (ref "C8") (pin "2") (pinfunction "2_2") (pintype "passive"))
      (node (ref "C9") (pin "2") (pinfunction "2_2") (pintype "passive"))
      (node (ref "D1") (pin "2") (pinfunction "A_2") (pintype "passive"))
      (node (ref "D2") (pin "2") (pinfunction "A_2") (pintype "passive"))
      (node (ref "D3") (pin "2") (pinfunction "A_2") (pintype "passive"))
      (node (ref "D4") (pin "2") (pinfunction "A_2") (pintype "passive"))
      (node (ref "D5") (pin "2") (pinfunction "A_2") (pintype "passive"))
      (node (ref "D6") (pin "2") (pinfunction "A_2") (pintype "passive"))
      (node (ref "J1") (pin "A1") (pinfunction "GND_A1") (pintype "bidirectional"))
      (node (ref "J1") (pin "A12") (pinfunction "GND_A12") (pintype "bidirectional"))
      (node (ref "J1") (pin "B1") (pinfunction "GND_B1") (pintype "bidirectional"))
      (node (ref "J1") (pin "B12") (pinfunction "GND_B12") (pintype "bidirectional"))
      (node (ref "JP2") (pin "15") (pinfunction "15_15") (pintype "passive"))
      (node (ref "JP2") (pin "16") (pinfunction "16_16") (pintype "passive"))
      (node (ref "L2") (pin "2") (pinfunction "2_2") (pintype "passive"))
      (node (ref "L5") (pin "1") (pinfunction "1_1") (pintype "passive"))
      (node (ref "Q1") (pin "2") (pinfunction "S_2") (pintype "passive"))
      (node (ref "R12") (pin "1") (pinfunction "1_1") (pintype "passive"))
      (node (ref "R13") (pin "1") (pinfunction "1_1") (pintype "passive"))
      (node (ref "R16") (pin "1") (pinfunction "1_1") (pintype "passive"))
      (node (ref "R18") (pin "2") (pinfunction "2_2") (pintype "passive"))
      (node (ref "R24") (pin "2") (pinfunction "2_2") (pintype "passive"))
      (node (ref "R26") (pin "2") (pinfunction "2_2") (pintype "passive"))
      (node (ref "R4") (pin "1") (pinfunction "1_1") (pintype "passive"))
      (node (ref "R5") (pin "2") (pinfunction "2_2") (pintype "passive"))
      (node (ref "U1") (pin "D4") (pinfunction "VSS_D4") (pintype "bidirectional"))
      (node (ref "U1") (pin "E10") (pinfunction "VSS_E10") (pintype "bidirectional"))
      (node (ref "U1") (pin "E11") (pinfunction "VSS_E11") (pintype "bidirectional"))
      (node (ref "U1") (pin "E12") (pinfunction "VSS_E12") (pintype "bidirectional"))
      (node (ref "U1") (pin "E13") (pinfunction "VSS_E13") (pintype "bidirectional"))
      (node (ref "U1") (pin "E14") (pinfunction "VSS_E14") (pintype "bidirectional"))
      (node (ref "U1") (pin "E15") (pinfunction "VSS_E15") (pintype "bidirectional"))
      (node (ref "U1") (pin "E4") (pinfunction "VSS_E4") (pintype "bidirectional"))
      (node (ref "U1") (pin "E5") (pinfunction "VSS_E5") (pintype "bidirectional"))
      (node (ref "U1") (pin "E6") (pinfunction "VSS_E6") (pintype "bidirectional"))
      (node (ref "U1") (pin "E7") (pinfunction "VSS_E7") (pintype "bidirectional"))
      (node (ref "U1") (pin "E8") (pinfunction "VSS_E8") (pintype "bidirectional"))
      (node (ref "U1") (pin "E9") (pinfunction "VSS_E9") (pintype "bidirectional"))
      (node (ref "U1") (pin "F10") (pinfunction "VSS_F10") (pintype "bidirectional"))
      (node (ref "U1") (pin "F11") (pinfunction "VSS_F11") (pintype "bidirectional"))
      (node (ref "U1") (pin "F12") (pinfunction "VSS_F12") (pintype "bidirectional"))
      (node (ref "U1") (pin "F13") (pinfunction "VSS_F13") (pintype "bidirectional"))
      (node (ref "U1") (pin "F14") (pinfunction "VSS_F14") (pintype "bidirectional"))
      (node (ref "U1") (pin "F15") (pinfunction "VSS_F15") (pintype "bidirectional"))
      (node (ref "U1") (pin "F4") (pinfunction "VSS_F4") (pintype "bidirectional"))
      (node (ref "U1") (pin "F5") (pinfunction "VSS_F5") (pintype "bidirectional"))
      (node (ref "U1") (pin "F6") (pinfunction "VSS_F6") (pintype "bidirectional"))
      (node (ref "U1") (pin "F7") (pinfunction "VSS_F7") (pintype "bidirectional"))
      (node (ref "U1") (pin "F8") (pinfunction "VSS_F8") (pintype "bidirectional"))
      (node (ref "U1") (pin "F9") (pinfunction "VSS_F9") (pintype "bidirectional"))
      (node (ref "U1") (pin "G11") (pinfunction "VSS_G11") (pintype "bidirectional"))
      (node (ref "U1") (pin "G12") (pinfunction "VSS_G12") (pintype "bidirectional"))
      (node (ref "U1") (pin "G13") (pinfunction "VSS_G13") (pintype "bidirectional"))
      (node (ref "U1") (pin "G14") (pinfunction "VSS_G14") (pintype "bidirectional"))
      (node (ref "U1") (pin "G15") (pinfunction "VSS_G15") (pintype "bidirectional"))
      (node (ref "U1") (pin "G5") (pinfunction "VSS_G5") (pintype "bidirectional"))
      (node (ref "U1") (pin "H13") (pinfunction "VSS_H13") (pintype "bidirectional"))
      (node (ref "U1") (pin "H14") (pinfunction "VSS_H14") (pintype "bidirectional"))
      (node (ref "U1") (pin "H15") (pinfunction "VSS_H15") (pintype "bidirectional"))
      (node (ref "U1") (pin "H5") (pinfunction "VSS_H5") (pintype "bidirectional"))
      (node (ref "U1") (pin "J13") (pinfunction "VSS_J13") (pintype "bidirectional"))
      (node (ref "U1") (pin "J14") (pinfunction "VSS_J14") (pintype "bidirectional"))
      (node (ref "U1") (pin "J15") (pinfunction "VSS_J15") (pintype "bidirectional"))
      (node (ref "U1") (pin "J16") (pinfunction "VSS_J16") (pintype "bidirectional"))
      (node (ref "U1") (pin "J5") (pinfunction "VSS_J5") (pintype "bidirectional"))
      (node (ref "U1") (pin "K13") (pinfunction "VSS_K13") (pintype "bidirectional"))
      (node (ref "U1") (pin "K14") (pinfunction "VSS_K14") (pintype "bidirectional"))
      (node (ref "U1") (pin "K15") (pinfunction "VSS_K15") (pintype "bidirectional"))
      (node (ref "U1") (pin "K16") (pinfunction "VSS_K16") (pintype "bidirectional"))
      (node (ref "U1") (pin "K5") (pinfunction "VSS_K5") (pintype "bidirectional"))
      (node (ref "U1") (pin "L13") (pinfunction "VSS_L13") (pintype "bidirectional"))
      (node (ref "U1") (pin "L14") (pinfunction "VSS_L14") (pintype "bidirectional"))
      (node (ref "U1") (pin "L15") (pinfunction "VSS_L15") (pintype "bidirectional"))
      (node (ref "U1") (pin "L5") (pinfunction "VSS_L5") (pintype "bidirectional"))
      (node (ref "U1") (pin "M10") (pinfunction "BYPASS_REG1V8_M10") (pintype "bidirectional"))
      (node (ref "U1") (pin "M11") (pinfunction "VSS_M11") (pintype "bidirectional"))
      (node (ref "U1") (pin "M12") (pinfunction "VSS_M12") (pintype "bidirectional"))
      (node (ref "U1") (pin "M13") (pinfunction "VSS_M13") (pintype "bidirectional"))
      (node (ref "U1") (pin "M14") (pinfunction "VSS_M14") (pintype "bidirectional"))
      (node (ref "U1") (pin "M15") (pinfunction "VSS_M15") (pintype "bidirectional"))
      (node (ref "U1") (pin "M5") (pinfunction "VSS_M5") (pintype "bidirectional"))
      (node (ref "U1") (pin "N10") (pinfunction "VSS_N10") (pintype "bidirectional"))
      (node (ref "U1") (pin "N11") (pinfunction "VSS_N11") (pintype "bidirectional"))
      (node (ref "U1") (pin "N12") (pinfunction "VSS_N12") (pintype "bidirectional"))
      (node (ref "U1") (pin "N13") (pinfunction "VSS_N13") (pintype "bidirectional"))
      (node (ref "U1") (pin "N14") (pinfunction "VSS_N14") (pintype "bidirectional"))
      (node (ref "U1") (pin "N15") (pinfunction "VSS_N15") (pintype "bidirectional"))
      (node (ref "U1") (pin "N5") (pinfunction "VSS_N5") (pintype "bidirectional"))
      (node (ref "U1") (pin "N6") (pinfunction "VSS_N6") (pintype "bidirectional"))
      (node (ref "U1") (pin "N7") (pinfunction "VSS_N7") (pintype "bidirectional"))
      (node (ref "U1") (pin "N8") (pinfunction "VSS_N8") (pintype "bidirectional"))
      (node (ref "U1") (pin "N9") (pinfunction "VSS_N9") (pintype "bidirectional"))
      (node (ref "U1") (pin "P5") (pinfunction "VSS_P5") (pintype "bidirectional"))
      (node (ref "U1") (pin "P6") (pinfunction "VSS_P6") (pintype "bidirectional"))
      (node (ref "U1") (pin "P7") (pinfunction "VSS_P7") (pintype "bidirectional"))
      (node (ref "U1") (pin "P8") (pinfunction "VSS_P8") (pintype "bidirectional"))
      (node (ref "U2") (pin "3") (pinfunction "GND_3") (pintype "input"))
      (node (ref "U3") (pin "3") (pinfunction "GND_3") (pintype "input"))
      (node (ref "U4") (pin "1") (pinfunction "GND_1") (pintype "power_in"))
      (node (ref "U4") (pin "12") (pinfunction "GND_12") (pintype "power_in"))
      (node (ref "U4") (pin "19") (pinfunction "GND_19") (pintype "power_in"))
      (node (ref "U4") (pin "21") (pinfunction "GND_21") (pintype "power_in"))
      (node (ref "U4") (pin "29") (pinfunction "GND_29") (pintype "power_in"))
      (node (ref "U4") (pin "32") (pinfunction "GND_(SR_PVSS)_32") (pintype "power_in"))
      (node (ref "U4") (pin "33") (pinfunction "GND_(SR_PVSS)_33") (pintype "power_in"))
      (node (ref "U4") (pin "35") (pinfunction "GND_35") (pintype "power_in"))
      (node (ref "U4") (pin "37") (pinfunction "LPO_IN_(32KHZ)_37") (pintype "input"))
      (node (ref "U4") (pin "40") (pinfunction "GND_40") (pintype "power_in"))
      (node (ref "U4") (pin "42") (pinfunction "GND_42") (pintype "power_in"))
      (node (ref "U4") (pin "43") (pinfunction "GND_43") (pintype "power_in"))
      (node (ref "U4") (pin "44") (pinfunction "GND_44") (pintype "power_in"))
      (node (ref "U4") (pin "45") (pinfunction "GND_45") (pintype "power_in"))
      (node (ref "U4") (pin "46") (pinfunction "GND_46") (pintype "power_in"))
      (node (ref "U5") (pin "GND") (pinfunction "GND_GND") (pintype "power_in"))
      (node (ref "U6") (pin "P$12") (pinfunction "GND_P$12") (pintype "power_in"))
      (node (ref "U6") (pin "P$3") (pinfunction "CP2_P$3") (pintype "input"))
      (node (ref "U6") (pin "P$6") (pinfunction "PR1_P$6") (pintype "input"))
      (node (ref "U7") (pin "12") (pinfunction "GND_12") (pintype "bidirectional"))
      (node (ref "U7") (pin "2") (pinfunction "GND_2") (pintype "bidirectional"))
      (node (ref "U7") (pin "3") (pinfunction "GND_3") (pintype "bidirectional"))
      (node (ref "U7") (pin "4") (pinfunction "GND_4") (pintype "bidirectional"))
      (node (ref "U7") (pin "6") (pinfunction "GND_6") (pintype "bidirectional"))
      (node (ref "X1") (pin "19") (pinfunction "19_19") (pintype "bidirectional"))
      (node (ref "X1") (pin "27") (pinfunction "27_27") (pintype "bidirectional"))
      (node (ref "X1") (pin "5") (pinfunction "5_5") (pintype "bidirectional"))
      (node (ref "X2") (pin "2") (pinfunction "1_2") (pintype "passive"))
      (node (ref "X3") (pin "6") (pinfunction "VSS_6") (pintype "power_in"))
      (node (ref "X3") (pin "9") (pinfunction "VSS_9") (pintype "power_in"))
      (node (ref "X3") (pin "P1") (pinfunction "SHIELD_P1") (pintype "passive"))
      (node (ref "X3") (pin "P2") (pinfunction "SHIELD_P2") (pintype "passive"))
      (node (ref "X3") (pin "P3") (pinfunction "SHIELD_P3") (pintype "passive"))
      (node (ref "X3") (pin "P4") (pinfunction "SHIELD_P4") (pintype "passive"))
    )
    (net (code "97") (name "Net-(ANT1-Pad1)") (class "Default")
      (node (ref "ANT1") (pin "1") (pinfunction "1_1") (pintype "input"))
      (node (ref "L4") (pin "2") (pinfunction "2_2") (pintype "passive"))
    )
    (net (code "98") (name "Net-(C14-Pad1)") (class "Default")
      (node (ref "C14") (pin "1") (pinfunction "1_1") (pintype "passive"))
      (node (ref "L4") (pin "1") (pinfunction "1_1") (pintype "passive"))
      (node (ref "L5") (pin "2") (pinfunction "2_2") (pintype "passive"))
    )
    (net (code "99") (name "Net-(D4-C)") (class "Default")
      (node (ref "D4") (pin "1") (pinfunction "C_1") (pintype "passive"))
      (node (ref "J1") (pin "A4") (pinfunction "VBUS_A4") (pintype "bidirectional"))
      (node (ref "J1") (pin "A9") (pinfunction "VBUS_A9") (pintype "bidirectional"))
      (node (ref "J1") (pin "B4") (pinfunction "VBUS_B4") (pintype "bidirectional"))
      (node (ref "J1") (pin "B9") (pinfunction "VBUS_B9") (pintype "bidirectional"))
      (node (ref "L1") (pin "1") (pinfunction "1_1") (pintype "passive"))
    )
    (net (code "100") (name "Net-(J1-SHLD-PadS_T1)") (class "Default")
      (node (ref "J1") (pin "S_T1") (pinfunction "SHLD_S_T1") (pintype "bidirectional"))
      (node (ref "J1") (pin "S_T2") (pinfunction "SHLD_S_T2") (pintype "bidirectional"))
      (node (ref "J1") (pin "S_T3") (pinfunction "SHLD_S_T3") (pintype "bidirectional"))
      (node (ref "J1") (pin "S_T4") (pinfunction "SHLD_S_T4") (pintype "bidirectional"))
      (node (ref "L2") (pin "1") (pinfunction "1_1") (pintype "passive"))
    )
    (net (code "101") (name "Net-(LED1-BLU)") (class "Default")
      (node (ref "LED1") (pin "B") (pinfunction "BLU_B") (pintype "bidirectional"))
      (node (ref "R20") (pin "2") (pinfunction "2_2") (pintype "passive"))
    )
    (net (code "102") (name "Net-(LED1-GRN)") (class "Default")
      (node (ref "LED1") (pin "G") (pinfunction "GRN_G") (pintype "bidirectional"))
      (node (ref "R21") (pin "2") (pinfunction "2_2") (pintype "passive"))
    )
    (net (code "103") (name "Net-(LED1-RED)") (class "Default")
      (node (ref "LED1") (pin "R") (pinfunction "RED_R") (pintype "bidirectional"))
      (node (ref "R19") (pin "2") (pinfunction "2_2") (pintype "passive"))
    )
    (net (code "104") (name "Net-(LED2-PadA)") (class "Default")
      (node (ref "LED2") (pin "A") (pinfunction "A_A") (pintype "passive"))
      (node (ref "LED3") (pin "C") (pinfunction "C_C") (pintype "passive"))
    )
    (net (code "105") (name "Net-(LED2-PadC)") (class "Default")
      (node (ref "LED2") (pin "C") (pinfunction "C_C") (pintype "passive"))
      (node (ref "R25") (pin "2") (pinfunction "2_2") (pintype "passive"))
    )
    (net (code "106") (name "Net-(Q1-D)") (class "Default")
      (node (ref "Q1") (pin "3") (pinfunction "D_3") (pintype "passive"))
      (node (ref "R25") (pin "1") (pinfunction "1_1") (pintype "passive"))
    )
    (net (code "107") (name "Net-(Q1-G)") (class "Default")
      (node (ref "Q1") (pin "1") (pinfunction "G_1") (pintype "passive"))
      (node (ref "R16") (pin "2") (pinfunction "2_2") (pintype "passive"))
      (node (ref "R22") (pin "2") (pinfunction "2_2") (pintype "passive"))
    )
    (net (code "108") (name "Net-(U1A-BOOT1)") (class "Default")
      (node (ref "R5") (pin "1") (pinfunction "1_1") (pintype "passive"))
      (node (ref "U1") (pin "H6") (pinfunction "BOOT1_H6") (pintype "bidirectional"))
    )
    (net (code "109") (name "Net-(U1A-EEPROM_WP)") (class "Default")
      (node (ref "SJ1") (pin "2") (pinfunction "2_2") (pintype "passive"))
      (node (ref "U1") (pin "P4") (pinfunction "EEPROM_WP_P4") (pintype "bidirectional"))
    )
    (net (code "110") (name "Net-(U1A-HSE_OSC_OE)") (class "Default")
      (node (ref "R4") (pin "2") (pinfunction "2_2") (pintype "passive"))
      (node (ref "U1") (pin "J1") (pinfunction "HSE_OSC_OE_J1") (pintype "bidirectional"))
    )
    (net (code "111") (name "Net-(U1A-PMIC_LDO5)") (class "Default")
      (node (ref "TP2") (pin "TP") (pinfunction "TP_TP") (pintype "input"))
      (node (ref "U1") (pin "G8") (pinfunction "PMIC_LDO5_G8") (pintype "bidirectional"))
    )
    (net (code "112") (name "Net-(U4-ANT)") (class "Default")
      (node (ref "C14") (pin "2") (pinfunction "2_2") (pintype "passive"))
      (node (ref "U4") (pin "41") (pinfunction "ANT_41") (pintype "passive"))
    )
    (net (code "113") (name "Net-(U4-SR_VLX)") (class "Default")
      (node (ref "L3") (pin "1") (pinfunction "1_1") (pintype "passive"))
      (node (ref "U4") (pin "34") (pinfunction "SR_VLX_34") (pintype "output"))
    )
    (net (code "114") (name "Net-(U4-VIN_LDO)") (class "Default")
      (node (ref "C15") (pin "1") (pinfunction "1_1") (pintype "passive"))
      (node (ref "L3") (pin "2") (pinfunction "2_2") (pintype "passive"))
      (node (ref "U4") (pin "31") (pinfunction "VIN_LDO_31") (pintype "power_in"))
    )
    (net (code "115") (name "Net-(U5-CLK_EX)") (class "Default")
      (node (ref "U5") (pin "P$11") (pinfunction "CLK_EX_P$11") (pintype "output"))
      (node (ref "X3") (pin "5") (pinfunction "CLK_5") (pintype "passive"))
    )
    (net (code "116") (name "Net-(U5-CMD_EX)") (class "Default")
      (node (ref "U5") (pin "P$12") (pinfunction "CMD_EX_P$12") (pintype "output"))
      (node (ref "X3") (pin "3") (pinfunction "CMD_3") (pintype "passive"))
    )
    (net (code "117") (name "Net-(U5-DAT0_EX)") (class "Default")
      (node (ref "U5") (pin "P$10") (pinfunction "DAT0_EX_P$10") (pintype "output"))
      (node (ref "X3") (pin "7") (pinfunction "DAT0_7") (pintype "passive"))
    )
    (net (code "118") (name "Net-(U5-DAT1_EX)") (class "Default")
      (node (ref "U5") (pin "P$9") (pinfunction "DAT1_EX_P$9") (pintype "output"))
      (node (ref "X3") (pin "8") (pinfunction "DAT1_8") (pintype "passive"))
    )
    (net (code "119") (name "Net-(U5-DAT2_EX)") (class "Default")
      (node (ref "U5") (pin "P$14") (pinfunction "DAT2_EX_P$14") (pintype "output"))
      (node (ref "X3") (pin "1") (pinfunction "DAT2_1") (pintype "passive"))
    )
    (net (code "120") (name "Net-(U5-DAT3_EX)") (class "Default")
      (node (ref "U5") (pin "P$13") (pinfunction "DAT3_EX_P$13") (pintype "output"))
      (node (ref "X3") (pin "2") (pinfunction "CD/DAT3^2_2") (pintype "passive"))
    )
    (net (code "121") (name "Net-(U6-ILIM)") (class "Default")
      (node (ref "R26") (pin "1") (pinfunction "1_1") (pintype "passive"))
      (node (ref "U6") (pin "P$10") (pinfunction "ILIM_P$10") (pintype "input"))
    )
    (net (code "122") (name "Net-(U6-OV1)") (class "Default")
      (node (ref "R23") (pin "2") (pinfunction "2_2") (pintype "passive"))
      (node (ref "R24") (pin "1") (pinfunction "1_1") (pintype "passive"))
      (node (ref "U6") (pin "P$5") (pinfunction "OV1_P$5") (pintype "input"))
    )
    (net (code "123") (name "Net-(U6-OV2)") (class "Default")
      (node (ref "R17") (pin "2") (pinfunction "2_2") (pintype "passive"))
      (node (ref "R18") (pin "1") (pinfunction "1_1") (pintype "passive"))
      (node (ref "U6") (pin "P$4") (pinfunction "OV2_P$4") (pintype "input"))
    )
    (net (code "124") (name "Net-(U6-SS)") (class "Default")
      (node (ref "C19") (pin "1") (pinfunction "1_1") (pintype "passive"))
      (node (ref "U6") (pin "P$11") (pinfunction "SS_P$11") (pintype "passive"))
    )
    (net (code "125") (name "VBAT") (class "Default")
      (node (ref "C12") (pin "1") (pinfunction "1_1") (pintype "passive"))
      (node (ref "C13") (pin "1") (pinfunction "1_1") (pintype "passive"))
      (node (ref "D6") (pin "1") (pinfunction "C_1") (pintype "passive"))
      (node (ref "JP2") (pin "14") (pinfunction "14_14") (pintype "passive"))
      (node (ref "R17") (pin "1") (pinfunction "1_1") (pintype "passive"))
      (node (ref "U6") (pin "P$2") (pinfunction "IN2_P$2") (pintype "power_in"))
      (node (ref "X2") (pin "1") (pinfunction "2_1") (pintype "passive"))
    )
    (net (code "126") (name "VBUS") (class "Default")
      (node (ref "C10") (pin "1") (pinfunction "1_1") (pintype "passive"))
      (node (ref "C11") (pin "1") (pinfunction "1_1") (pintype "passive"))
      (node (ref "L1") (pin "2") (pinfunction "2_2") (pintype "passive"))
      (node (ref "R23") (pin "1") (pinfunction "1_1") (pintype "passive"))
      (node (ref "U6") (pin "P$7") (pinfunction "IN1_P$7") (pintype "power_in"))
    )
    (net (code "127") (name "VBUS_SW") (class "Default")
      (node (ref "C3") (pin "1") (pinfunction "1_1") (pintype "passive"))
      (node (ref "C4") (pin "1") (pinfunction "1_1") (pintype "passive"))
      (node (ref "D5") (pin "1") (pinfunction "C_1") (pintype "passive"))
      (node (ref "JP1") (pin "14") (pinfunction "14_14") (pintype "passive"))
      (node (ref "U1") (pin "J8") (pinfunction "PMIC_BSTOUT_J8") (pintype "bidirectional"))
      (node (ref "U1") (pin "J9") (pinfunction "PMIC_BSTOUT_J9") (pintype "bidirectional"))
    )
    (net (code "128") (name "VDD") (class "Default")
      (node (ref "U1") (pin "G7") (pinfunction "VDD_G7") (pintype "bidirectional"))
      (node (ref "U1") (pin "H7") (pinfunction "VDD_H7") (pintype "bidirectional"))
      (node (ref "U1") (pin "J7") (pinfunction "VDD_J7") (pintype "bidirectional"))
      (node (ref "U1") (pin "K3") (pinfunction "VBAT_K3") (pintype "bidirectional"))
      (node (ref "U1") (pin "K4") (pinfunction "VDD_K4") (pintype "bidirectional"))
      (node (ref "U1") (pin "K7") (pinfunction "VDD_K7") (pintype "bidirectional"))
      (node (ref "U1") (pin "L4") (pinfunction "VDD_L4") (pintype "bidirectional"))
      (node (ref "U1") (pin "L7") (pinfunction "VDD_L7") (pintype "bidirectional"))
      (node (ref "U1") (pin "M4") (pinfunction "VDD_M4") (pintype "bidirectional"))
      (node (ref "U1") (pin "M7") (pinfunction "VDD_M7") (pintype "bidirectional"))
    )
    (net (code "129") (name "VIN") (class "Default")
      (node (ref "C1") (pin "2") (pinfunction "2_2") (pintype "passive"))
      (node (ref "C2") (pin "2") (pinfunction "2_2") (pintype "passive"))
      (node (ref "C20") (pin "1") (pinfunction "1_1") (pintype "passive"))
      (node (ref "U1") (pin "G1") (pinfunction "VIN_G1") (pintype "bidirectional"))
      (node (ref "U1") (pin "G2") (pinfunction "VIN_G2") (pintype "bidirectional"))
      (node (ref "U1") (pin "G3") (pinfunction "PMIC_LDO25IN_G3") (pintype "bidirectional"))
      (node (ref "U1") (pin "H1") (pinfunction "VIN_H1") (pintype "bidirectional"))
      (node (ref "U1") (pin "H2") (pinfunction "VIN_H2") (pintype "bidirectional"))
      (node (ref "U1") (pin "H8") (pinfunction "PMIC_SWIN_H8") (pintype "bidirectional"))
      (node (ref "U1") (pin "H9") (pinfunction "PMIC_SWIN_H9") (pintype "bidirectional"))
      (node (ref "U1") (pin "L8") (pinfunction "PMIC_BSTIN_L8") (pintype "bidirectional"))
      (node (ref "U1") (pin "L9") (pinfunction "PMIC_BSTIN_L9") (pintype "bidirectional"))
      (node (ref "U1") (pin "M8") (pinfunction "PMIC_BSTIN_M8") (pintype "bidirectional"))
      (node (ref "U1") (pin "M9") (pinfunction "PMIC_BSTIN_M9") (pintype "bidirectional"))
      (node (ref "U6") (pin "P$1") (pinfunction "OUT_P$1") (pintype "power_in"))
      (node (ref "U6") (pin "P$8") (pinfunction "OUT_P$8") (pintype "power_in"))
    )
    (net (code "130") (name "VSSA") (class "Default")
      (node (ref "U1") (pin "K1") (pinfunction "VSSA_K1") (pintype "bidirectional"))
      (node (ref "U1") (pin "K2") (pinfunction "VREF-_K2") (pintype "bidirectional"))
    )
    (net (code "131") (name "unconnected-(H1-MOUNT-PadB2,8)") (class "Default")
      (node (ref "H1") (pin "B2,8") (pinfunction "MOUNT_B2,8") (pintype "passive"))
    )
    (net (code "132") (name "unconnected-(H2-MOUNT-PadB2,8)") (class "Default")
      (node (ref "H2") (pin "B2,8") (pinfunction "MOUNT_B2,8") (pintype "passive"))
    )
    (net (code "133") (name "unconnected-(J1-RX1+-PadB11)") (class "Default")
      (node (ref "J1") (pin "B11") (pinfunction "RX1+_B11") (pintype "bidirectional"))
    )
    (net (code "134") (name "unconnected-(J1-RX1--PadB10)") (class "Default")
      (node (ref "J1") (pin "B10") (pinfunction "RX1-_B10") (pintype "bidirectional"))
    )
    (net (code "135") (name "unconnected-(J1-RX2+-PadA11)") (class "Default")
      (node (ref "J1") (pin "A11") (pinfunction "RX2+_A11") (pintype "bidirectional"))
    )
    (net (code "136") (name "unconnected-(J1-RX2--PadA10)") (class "Default")
      (node (ref "J1") (pin "A10") (pinfunction "RX2-_A10") (pintype "bidirectional"))
    )
    (net (code "137") (name "unconnected-(J1-SBU1-PadA8)") (class "Default")
      (node (ref "J1") (pin "A8") (pinfunction "SBU1_A8") (pintype "bidirectional"))
    )
    (net (code "138") (name "unconnected-(J1-SBU2-PadB8)") (class "Default")
      (node (ref "J1") (pin "B8") (pinfunction "SBU2_B8") (pintype "bidirectional"))
    )
    (net (code "139") (name "unconnected-(J1-TX1+-PadA2)") (class "Default")
      (node (ref "J1") (pin "A2") (pinfunction "TX1+_A2") (pintype "bidirectional"))
    )
    (net (code "140") (name "unconnected-(J1-TX1--PadA3)") (class "Default")
      (node (ref "J1") (pin "A3") (pinfunction "TX1-_A3") (pintype "bidirectional"))
    )
    (net (code "141") (name "unconnected-(J1-TX2+-PadB2)") (class "Default")
      (node (ref "J1") (pin "B2") (pinfunction "TX2+_B2") (pintype "bidirectional"))
    )
    (net (code "142") (name "unconnected-(J1-TX2--PadB3)") (class "Default")
      (node (ref "J1") (pin "B3") (pinfunction "TX2-_B3") (pintype "bidirectional"))
    )
    (net (code "143") (name "unconnected-(U1A-PMIC_LDO1-PadJ4)") (class "Default")
      (node (ref "U1") (pin "J4") (pinfunction "PMIC_LDO1_J4") (pintype "bidirectional"))
    )
    (net (code "144") (name "unconnected-(U1A-PMIC_LDO2-PadG4)") (class "Default")
      (node (ref "U1") (pin "G4") (pinfunction "PMIC_LDO2_G4") (pintype "bidirectional"))
    )
    (net (code "145") (name "unconnected-(U1A-PMIC_LDO6-PadH4)") (class "Default")
      (node (ref "U1") (pin "H4") (pinfunction "PMIC_LDO6_H4") (pintype "bidirectional"))
    )
    (net (code "146") (name "unconnected-(U1A-PMIC_SWOUT-PadG9)") (class "Default")
      (node (ref "U1") (pin "G9") (pinfunction "PMIC_SWOUT_G9") (pintype "bidirectional"))
    )
    (net (code "147") (name "unconnected-(U1A-PMIC_SWOUT-PadG10)") (class "Default")
      (node (ref "U1") (pin "G10") (pinfunction "PMIC_SWOUT_G10") (pintype "bidirectional"))
    )
    (net (code "148") (name "unconnected-(U1A-PMIC_VBUSOTG-PadK8)") (class "Default")
      (node (ref "U1") (pin "K8") (pinfunction "PMIC_VBUSOTG_K8") (pintype "bidirectional"))
    )
    (net (code "149") (name "unconnected-(U1B-PA1-PadC16)") (class "Default")
      (node (ref "U1") (pin "C16") (pinfunction "PA1_C16") (pintype "bidirectional"))
    )
    (net (code "150") (name "unconnected-(U1B-PA3-PadA5)") (class "Default")
      (node (ref "U1") (pin "A5") (pinfunction "PA3_A5") (pintype "bidirectional"))
    )
    (net (code "151") (name "unconnected-(U1B-PA9-PadU12)") (class "Default")
      (node (ref "U1") (pin "U12") (pinfunction "PA9_U12") (pintype "bidirectional"))
    )
    (net (code "152") (name "unconnected-(U1B-PA10-PadL16)") (class "Default")
      (node (ref "U1") (pin "L16") (pinfunction "PA10_L16") (pintype "bidirectional"))
    )
    (net (code "153") (name "unconnected-(U1B-PA13-PadA3)") (class "Default")
      (node (ref "U1") (pin "A3") (pinfunction "PA13_A3") (pintype "bidirectional"))
    )
    (net (code "154") (name "unconnected-(U1B-PA14-PadB3)") (class "Default")
      (node (ref "U1") (pin "B3") (pinfunction "PA14_B3") (pintype "bidirectional"))
    )
    (net (code "155") (name "unconnected-(U1B-PB0-PadA11)") (class "Default")
      (node (ref "U1") (pin "A11") (pinfunction "PB0_A11") (pintype "bidirectional"))
    )
    (net (code "156") (name "unconnected-(U1B-PB1-PadB11)") (class "Default")
      (node (ref "U1") (pin "B11") (pinfunction "PB1_B11") (pintype "bidirectional"))
    )
    (net (code "157") (name "unconnected-(U1B-PB6-PadH18)") (class "Default")
      (node (ref "U1") (pin "H18") (pinfunction "PB6_H18") (pintype "bidirectional"))
    )
    (net (code "158") (name "unconnected-(U1B-PB9-PadU13)") (class "Default")
      (node (ref "U1") (pin "U13") (pinfunction "PB9_U13") (pintype "bidirectional"))
    )
    (net (code "159") (name "unconnected-(U1B-PB11-PadA9)") (class "Default")
      (node (ref "U1") (pin "A9") (pinfunction "PB11_A9") (pintype "bidirectional"))
    )
    (net (code "160") (name "unconnected-(U1B-PC0-PadA17)") (class "Default")
      (node (ref "U1") (pin "A17") (pinfunction "PC0_A17") (pintype "bidirectional"))
    )
    (net (code "161") (name "unconnected-(U1B-PC1-PadB15)") (class "Default")
      (node (ref "U1") (pin "B15") (pinfunction "PC1_B15") (pintype "bidirectional"))
    )
    (net (code "162") (name "unconnected-(U1B-PC4-PadB12)") (class "Default")
      (node (ref "U1") (pin "B12") (pinfunction "PC4_B12") (pintype "bidirectional"))
    )
    (net (code "163") (name "unconnected-(U1B-PC5-PadC12)") (class "Default")
      (node (ref "U1") (pin "C12") (pinfunction "PC5_C12") (pintype "bidirectional"))
    )
    (net (code "164") (name "unconnected-(U1B-PC6-PadR18)") (class "Default")
      (node (ref "U1") (pin "R18") (pinfunction "PC6_R18") (pintype "bidirectional"))
    )
    (net (code "165") (name "unconnected-(U1B-PC7-PadR16)") (class "Default")
      (node (ref "U1") (pin "R16") (pinfunction "PC7_R16") (pintype "bidirectional"))
    )
    (net (code "166") (name "unconnected-(U1B-PD11-PadE18)") (class "Default")
      (node (ref "U1") (pin "E18") (pinfunction "PD11_E18") (pintype "bidirectional"))
    )
    (net (code "167") (name "unconnected-(U1B-PD15-PadA2)") (class "Default")
      (node (ref "U1") (pin "A2") (pinfunction "PD15_A2") (pintype "bidirectional"))
    )
    (net (code "168") (name "unconnected-(U1C-PE1-PadT7)") (class "Default")
      (node (ref "U1") (pin "T7") (pinfunction "PE1_T7") (pintype "bidirectional"))
    )
    (net (code "169") (name "unconnected-(U1C-PE2-PadA6)") (class "Default")
      (node (ref "U1") (pin "A6") (pinfunction "PE2_A6") (pintype "bidirectional"))
    )
    (net (code "170") (name "unconnected-(U1C-PE4-PadR17)") (class "Default")
      (node (ref "U1") (pin "R17") (pinfunction "PE4_R17") (pintype "bidirectional"))
    )
    (net (code "171") (name "unconnected-(U1C-PE5-PadV15)") (class "Default")
      (node (ref "U1") (pin "V15") (pinfunction "PE5_V15") (pintype "bidirectional"))
    )
    (net (code "172") (name "unconnected-(U1C-PE7-PadD17)") (class "Default")
      (node (ref "U1") (pin "D17") (pinfunction "PE7_D17") (pintype "bidirectional"))
    )
    (net (code "173") (name "unconnected-(U1C-PE12-PadU5)") (class "Default")
      (node (ref "U1") (pin "U5") (pinfunction "PE12_U5") (pintype "bidirectional"))
    )
    (net (code "174") (name "unconnected-(U1C-PE13-PadT5)") (class "Default")
      (node (ref "U1") (pin "T5") (pinfunction "PE13_T5") (pintype "bidirectional"))
    )
    (net (code "175") (name "unconnected-(U1C-PE14-PadV4)") (class "Default")
      (node (ref "U1") (pin "V4") (pinfunction "PE14_V4") (pintype "bidirectional"))
    )
    (net (code "176") (name "unconnected-(U1C-PE15-PadU4)") (class "Default")
      (node (ref "U1") (pin "U4") (pinfunction "PE15_U4") (pintype "bidirectional"))
    )
    (net (code "177") (name "unconnected-(U1C-PF0-PadU8)") (class "Default")
      (node (ref "U1") (pin "U8") (pinfunction "PF0_U8") (pintype "bidirectional"))
    )
    (net (code "178") (name "unconnected-(U1C-PF2-PadT18)") (class "Default")
      (node (ref "U1") (pin "T18") (pinfunction "PF2_T18") (pintype "bidirectional"))
    )
    (net (code "179") (name "unconnected-(U1C-PF3-PadC6)") (class "Default")
      (node (ref "U1") (pin "C6") (pinfunction "PF3_C6") (pintype "bidirectional"))
    )
    (net (code "180") (name "unconnected-(U1C-PF5-PadT8)") (class "Default")
      (node (ref "U1") (pin "T8") (pinfunction "PF5_T8") (pintype "bidirectional"))
    )
    (net (code "181") (name "unconnected-(U1C-PF6-PadF18)") (class "Default")
      (node (ref "U1") (pin "F18") (pinfunction "PF6_F18") (pintype "bidirectional"))
    )
    (net (code "182") (name "unconnected-(U1C-PF7-PadG16)") (class "Default")
      (node (ref "U1") (pin "G16") (pinfunction "PF7_G16") (pintype "bidirectional"))
    )
    (net (code "183") (name "unconnected-(U1C-PF8-PadG17)") (class "Default")
      (node (ref "U1") (pin "G17") (pinfunction "PF8_G17") (pintype "bidirectional"))
    )
    (net (code "184") (name "unconnected-(U1C-PF9-PadG18)") (class "Default")
      (node (ref "U1") (pin "G18") (pinfunction "PF9_G18") (pintype "bidirectional"))
    )
    (net (code "185") (name "unconnected-(U1C-PF10-PadH16)") (class "Default")
      (node (ref "U1") (pin "H16") (pinfunction "PF10_H16") (pintype "bidirectional"))
    )
    (net (code "186") (name "unconnected-(U1C-PF11-PadB18)") (class "Default")
      (node (ref "U1") (pin "B18") (pinfunction "PF11_B18") (pintype "bidirectional"))
    )
    (net (code "187") (name "unconnected-(U1C-PF12-PadC11)") (class "Default")
      (node (ref "U1") (pin "C11") (pinfunction "PF12_C11") (pintype "bidirectional"))
    )
    (net (code "188") (name "unconnected-(U1C-PF15-PadC10)") (class "Default")
      (node (ref "U1") (pin "C10") (pinfunction "PF15_C10") (pintype "bidirectional"))
    )
    (net (code "189") (name "unconnected-(U1C-PG0-PadC8)") (class "Default")
      (node (ref "U1") (pin "C8") (pinfunction "PG0_C8") (pintype "bidirectional"))
    )
    (net (code "190") (name "unconnected-(U1C-PG1-PadB8)") (class "Default")
      (node (ref "U1") (pin "B8") (pinfunction "PG1_B8") (pintype "bidirectional"))
    )
    (net (code "191") (name "unconnected-(U1C-PG2-PadA8)") (class "Default")
      (node (ref "U1") (pin "A8") (pinfunction "PG2_A8") (pintype "bidirectional"))
    )
    (net (code "192") (name "unconnected-(U1C-PG3-PadC9)") (class "Default")
      (node (ref "U1") (pin "C9") (pinfunction "PG3_C9") (pintype "bidirectional"))
    )
    (net (code "193") (name "unconnected-(U1C-PG4-PadB9)") (class "Default")
      (node (ref "U1") (pin "B9") (pinfunction "PG4_B9") (pintype "bidirectional"))
    )
    (net (code "194") (name "unconnected-(U1C-PG5-PadC15)") (class "Default")
      (node (ref "U1") (pin "C15") (pinfunction "PG5_C15") (pintype "bidirectional"))
    )
    (net (code "195") (name "unconnected-(U1C-PG7-PadH17)") (class "Default")
      (node (ref "U1") (pin "H17") (pinfunction "PG7_H17") (pintype "bidirectional"))
    )
    (net (code "196") (name "unconnected-(U1C-PG9-PadM17)") (class "Default")
      (node (ref "U1") (pin "M17") (pinfunction "PG9_M17") (pintype "bidirectional"))
    )
    (net (code "197") (name "unconnected-(U1C-PG10-PadC18)") (class "Default")
      (node (ref "U1") (pin "C18") (pinfunction "PG10_C18") (pintype "bidirectional"))
    )
    (net (code "198") (name "unconnected-(U1C-PG12-PadA4)") (class "Default")
      (node (ref "U1") (pin "A4") (pinfunction "PG12_A4") (pintype "bidirectional"))
    )
    (net (code "199") (name "unconnected-(U1C-PG13-PadB7)") (class "Default")
      (node (ref "U1") (pin "B7") (pinfunction "PG13_B7") (pintype "bidirectional"))
    )
    (net (code "200") (name "unconnected-(U1C-PG14-PadA7)") (class "Default")
      (node (ref "U1") (pin "A7") (pinfunction "PG14_A7") (pintype "bidirectional"))
    )
    (net (code "201") (name "unconnected-(U1C-PG15-PadV9)") (class "Default")
      (node (ref "U1") (pin "V9") (pinfunction "PG15_V9") (pintype "bidirectional"))
    )
    (net (code "202") (name "unconnected-(U1C-PH2-PadB13)") (class "Default")
      (node (ref "U1") (pin "B13") (pinfunction "PH2_B13") (pintype "bidirectional"))
    )
    (net (code "203") (name "unconnected-(U1C-PH3-PadC13)") (class "Default")
      (node (ref "U1") (pin "C13") (pinfunction "PH3_C13") (pintype "bidirectional"))
    )
    (net (code "204") (name "unconnected-(U1C-PH5-PadT6)") (class "Default")
      (node (ref "U1") (pin "T6") (pinfunction "PH5_T6") (pintype "bidirectional"))
    )
    (net (code "205") (name "unconnected-(U1C-PH6-PadB5)") (class "Default")
      (node (ref "U1") (pin "B5") (pinfunction "PH6_B5") (pintype "bidirectional"))
    )
    (net (code "206") (name "unconnected-(U1C-PH7-PadC5)") (class "Default")
      (node (ref "U1") (pin "C5") (pinfunction "PH7_C5") (pintype "bidirectional"))
    )
    (net (code "207") (name "unconnected-(U1C-PH13-PadU1)") (class "Default")
      (node (ref "U1") (pin "U1") (pinfunction "PH13_U1") (pintype "bidirectional"))
    )
    (net (code "208") (name "unconnected-(U1C-PI0-PadT3)") (class "Default")
      (node (ref "U1") (pin "T3") (pinfunction "PI0_T3") (pintype "bidirectional"))
    )
    (net (code "209") (name "unconnected-(U1C-PI7-PadN3)") (class "Default")
      (node (ref "U1") (pin "N3") (pinfunction "PI7_N3") (pintype "bidirectional"))
    )
    (net (code "210") (name "unconnected-(U1C-PI9-PadC2)") (class "Default")
      (node (ref "U1") (pin "C2") (pinfunction "PI9_C2") (pintype "bidirectional"))
    )
    (net (code "211") (name "unconnected-(U1C-PI10-PadB4)") (class "Default")
      (node (ref "U1") (pin "B4") (pinfunction "PI10_B4") (pintype "bidirectional"))
    )
    (net (code "212") (name "unconnected-(U1C-PI11-PadC4)") (class "Default")
      (node (ref "U1") (pin "C4") (pinfunction "PI11_C4") (pintype "bidirectional"))
    )
    (net (code "213") (name "unconnected-(U1C-PZ4{slash}PMIC_SCL-PadE2)") (class "Default")
      (node (ref "U1") (pin "E2") (pinfunction "PZ4/PMIC_SCL_E2") (pintype "bidirectional"))
    )
    (net (code "214") (name "unconnected-(U1C-PZ5{slash}PMIC_SDA-PadE3)") (class "Default")
      (node (ref "U1") (pin "E3") (pinfunction "PZ5/PMIC_SDA_E3") (pintype "bidirectional"))
    )
    (net (code "215") (name "unconnected-(U1D-ANA1-PadL2)") (class "Default")
      (node (ref "U1") (pin "L2") (pinfunction "ANA1_L2") (pintype "bidirectional"))
    )
    (net (code "216") (name "unconnected-(U1D-DSI_CKN-PadP16)") (class "Default")
      (node (ref "U1") (pin "P16") (pinfunction "DSI_CKN_P16") (pintype "bidirectional"))
    )
    (net (code "217") (name "unconnected-(U1D-DSI_CKP-PadN16)") (class "Default")
      (node (ref "U1") (pin "N16") (pinfunction "DSI_CKP_N16") (pintype "bidirectional"))
    )
    (net (code "218") (name "unconnected-(U1D-DSI_D0N-PadP18)") (class "Default")
      (node (ref "U1") (pin "P18") (pinfunction "DSI_D0N_P18") (pintype "bidirectional"))
    )
    (net (code "219") (name "unconnected-(U1D-DSI_D0P-PadP17)") (class "Default")
      (node (ref "U1") (pin "P17") (pinfunction "DSI_D0P_P17") (pintype "bidirectional"))
    )
    (net (code "220") (name "unconnected-(U1D-DSI_D1N-PadN18)") (class "Default")
      (node (ref "U1") (pin "N18") (pinfunction "DSI_D1N_N18") (pintype "bidirectional"))
    )
    (net (code "221") (name "unconnected-(U1D-DSI_D1P-PadN17)") (class "Default")
      (node (ref "U1") (pin "N17") (pinfunction "DSI_D1P_N17") (pintype "bidirectional"))
    )
    (net (code "222") (name "unconnected-(U1D-JTDI-PadR13)") (class "Default")
      (node (ref "U1") (pin "R13") (pinfunction "JTDI_R13") (pintype "bidirectional"))
    )
    (net (code "223") (name "unconnected-(U1D-NJTRST-PadR11)") (class "Default")
      (node (ref "U1") (pin "R11") (pinfunction "NJTRST_R11") (pintype "bidirectional"))
    )
    (net (code "224") (name "unconnected-(U1D-OTG_VBUS-PadK9)") (class "Default")
      (node (ref "U1") (pin "K9") (pinfunction "OTG_VBUS_K9") (pintype "bidirectional"))
    )
    (net (code "225") (name "unconnected-(U1D-VDDA-PadM1)") (class "Default")
      (node (ref "U1") (pin "M1") (pinfunction "VDDA_M1") (pintype "bidirectional"))
    )
    (net (code "226") (name "unconnected-(U1F-HSE_OSC_TP-PadJ2)") (class "Default")
      (node (ref "U1") (pin "J2") (pinfunction "HSE_OSC_TP_J2") (pintype "bidirectional"))
    )
    (net (code "227") (name "unconnected-(U1F-LSE_OSC_TP-PadN2)") (class "Default")
      (node (ref "U1") (pin "N2") (pinfunction "LSE_OSC_TP_N2") (pintype "bidirectional"))
    )
    (net (code "228") (name "unconnected-(U1F-NRST_CORE-PadN4)") (class "Default")
      (node (ref "U1") (pin "N4") (pinfunction "NRST_CORE_N4") (pintype "bidirectional"))
    )
    (net (code "229") (name "unconnected-(U1F-PA0{slash}PMIC_INTN-PadL3)") (class "Default")
      (node (ref "U1") (pin "L3") (pinfunction "PA0/PMIC_INTN_L3") (pintype "bidirectional"))
    )
    (net (code "230") (name "unconnected-(U1F-PC13{slash}PMIC_WAKEUP-PadD6)") (class "Default")
      (node (ref "U1") (pin "D6") (pinfunction "PC13/PMIC_WAKEUP_D6") (pintype "bidirectional"))
    )
    (net (code "231") (name "unconnected-(U1F-PDR_ON-PadM6)") (class "Default")
      (node (ref "U1") (pin "M6") (pinfunction "PDR_ON_M6") (pintype "bidirectional"))
    )
    (net (code "232") (name "unconnected-(U1F-PDR_ON_CORE-PadL6)") (class "Default")
      (node (ref "U1") (pin "L6") (pinfunction "PDR_ON_CORE_L6") (pintype "bidirectional"))
    )
    (net (code "233") (name "unconnected-(U1F-PWR_LP-PadK6)") (class "Default")
      (node (ref "U1") (pin "K6") (pinfunction "PWR_LP_K6") (pintype "bidirectional"))
    )
    (net (code "234") (name "unconnected-(U1F-PWR_ON{slash}PMIC_PWRCTRL-PadD5)") (class "Default")
      (node (ref "U1") (pin "D5") (pinfunction "PWR_ON/PMIC_PWRCTRL_D5") (pintype "bidirectional"))
    )
    (net (code "235") (name "unconnected-(U1F-RSVD-PadN1)") (class "Default")
      (node (ref "U1") (pin "N1") (pinfunction "RSVD_N1") (pintype "bidirectional"))
    )
    (net (code "236") (name "unconnected-(U1F-VDD1V2_DSI_REG-PadR6)") (class "Default")
      (node (ref "U1") (pin "R6") (pinfunction "VDD1V2_DSI_REG_R6") (pintype "bidirectional"))
    )
    (net (code "237") (name "unconnected-(U1F-VDD3V3_USB-PadR5)") (class "Default")
      (node (ref "U1") (pin "R5") (pinfunction "VDD3V3_USB_R5") (pintype "bidirectional"))
    )
    (net (code "238") (name "unconnected-(U1F-VDDA1V1_REG-PadR8)") (class "Default")
      (node (ref "U1") (pin "R8") (pinfunction "VDDA1V1_REG_R8") (pintype "bidirectional"))
    )
    (net (code "239") (name "unconnected-(U1F-VDDA1V8_REG-PadR7)") (class "Default")
      (node (ref "U1") (pin "R7") (pinfunction "VDDA1V8_REG_R7") (pintype "bidirectional"))
    )
    (net (code "240") (name "unconnected-(U1F-VDD_CORE-PadR4)") (class "Default")
      (node (ref "U1") (pin "R4") (pinfunction "VDD_CORE_R4") (pintype "bidirectional"))
    )
    (net (code "241") (name "unconnected-(U1F-VDD_DDR-PadK12)") (class "Default")
      (node (ref "U1") (pin "K12") (pinfunction "VDD_DDR_K12") (pintype "bidirectional"))
    )
    (net (code "242") (name "unconnected-(U1F-VREF_DDR-PadL12)") (class "Default")
      (node (ref "U1") (pin "L12") (pinfunction "VREF_DDR_L12") (pintype "bidirectional"))
    )
    (net (code "243") (name "unconnected-(U1F-VTT_DDR-PadJ12)") (class "Default")
      (node (ref "U1") (pin "J12") (pinfunction "VTT_DDR_J12") (pintype "bidirectional"))
    )
    (net (code "244") (name "unconnected-(U2-NC-Pad4)") (class "Default")
      (node (ref "U2") (pin "4") (pinfunction "NC_4") (pintype "no_connect"))
    )
    (net (code "245") (name "unconnected-(U3-NC-Pad4)") (class "Default")
      (node (ref "U3") (pin "4") (pinfunction "NC_4") (pintype "no_connect"))
    )
    (net (code "246") (name "unconnected-(U4-BT_GPIO_3-Pad6)") (class "Default")
      (node (ref "U4") (pin "6") (pinfunction "BT_GPIO_3_6") (pintype "bidirectional"))
    )
    (net (code "247") (name "unconnected-(U4-BT_GPIO_4-Pad7)") (class "Default")
      (node (ref "U4") (pin "7") (pinfunction "BT_GPIO_4_7") (pintype "bidirectional"))
    )
    (net (code "248") (name "unconnected-(U4-BT_GPIO_5-Pad13)") (class "Default")
      (node (ref "U4") (pin "13") (pinfunction "BT_GPIO_5_13") (pintype "bidirectional"))
    )
    (net (code "249") (name "unconnected-(U4-BT_I2S_DO-Pad16)") (class "Default")
      (node (ref "U4") (pin "16") (pinfunction "BT_I2S_DO_16") (pintype "bidirectional"))
    )
    (net (code "250") (name "unconnected-(U4-BT_PCM_CLK-Pad11)") (class "Default")
      (node (ref "U4") (pin "11") (pinfunction "BT_PCM_CLK_11") (pintype "bidirectional"))
    )
    (net (code "251") (name "unconnected-(U4-BT_PCM_IN-Pad9)") (class "Default")
      (node (ref "U4") (pin "9") (pinfunction "BT_PCM_IN_9") (pintype "input"))
    )
    (net (code "252") (name "unconnected-(U4-BT_PCM_OUT-Pad10)") (class "Default")
      (node (ref "U4") (pin "10") (pinfunction "BT_PCM_OUT_10") (pintype "output"))
    )
    (net (code "253") (name "unconnected-(U4-BT_PCM_SYNC-Pad8)") (class "Default")
      (node (ref "U4") (pin "8") (pinfunction "BT_PCM_SYNC_8") (pintype "bidirectional"))
    )
    (net (code "254") (name "unconnected-(U4-WL_GPIO_1-Pad18)") (class "Default")
      (node (ref "U4") (pin "18") (pinfunction "WL_GPIO_1_18") (pintype "bidirectional"))
    )
    (net (code "255") (name "unconnected-(U4-WL_GPIO_2-Pad17)") (class "Default")
      (node (ref "U4") (pin "17") (pinfunction "WL_GPIO_2_17") (pintype "bidirectional"))
    )
    (net (code "256") (name "unconnected-(U4-WL_GPIO_4-Pad15)") (class "Default")
      (node (ref "U4") (pin "15") (pinfunction "WL_GPIO_4_15") (pintype "bidirectional"))
    )
    (net (code "257") (name "unconnected-(U5-RDAT3_GND-PadP$2)") (class "Default")
      (node (ref "U5") (pin "P$2") (pinfunction "RDAT3_GND_P$2") (pintype "passive"))
    )
  )
)
